# Sheet1.net
KiCad netlist of a schematic drawn in Altium Designer
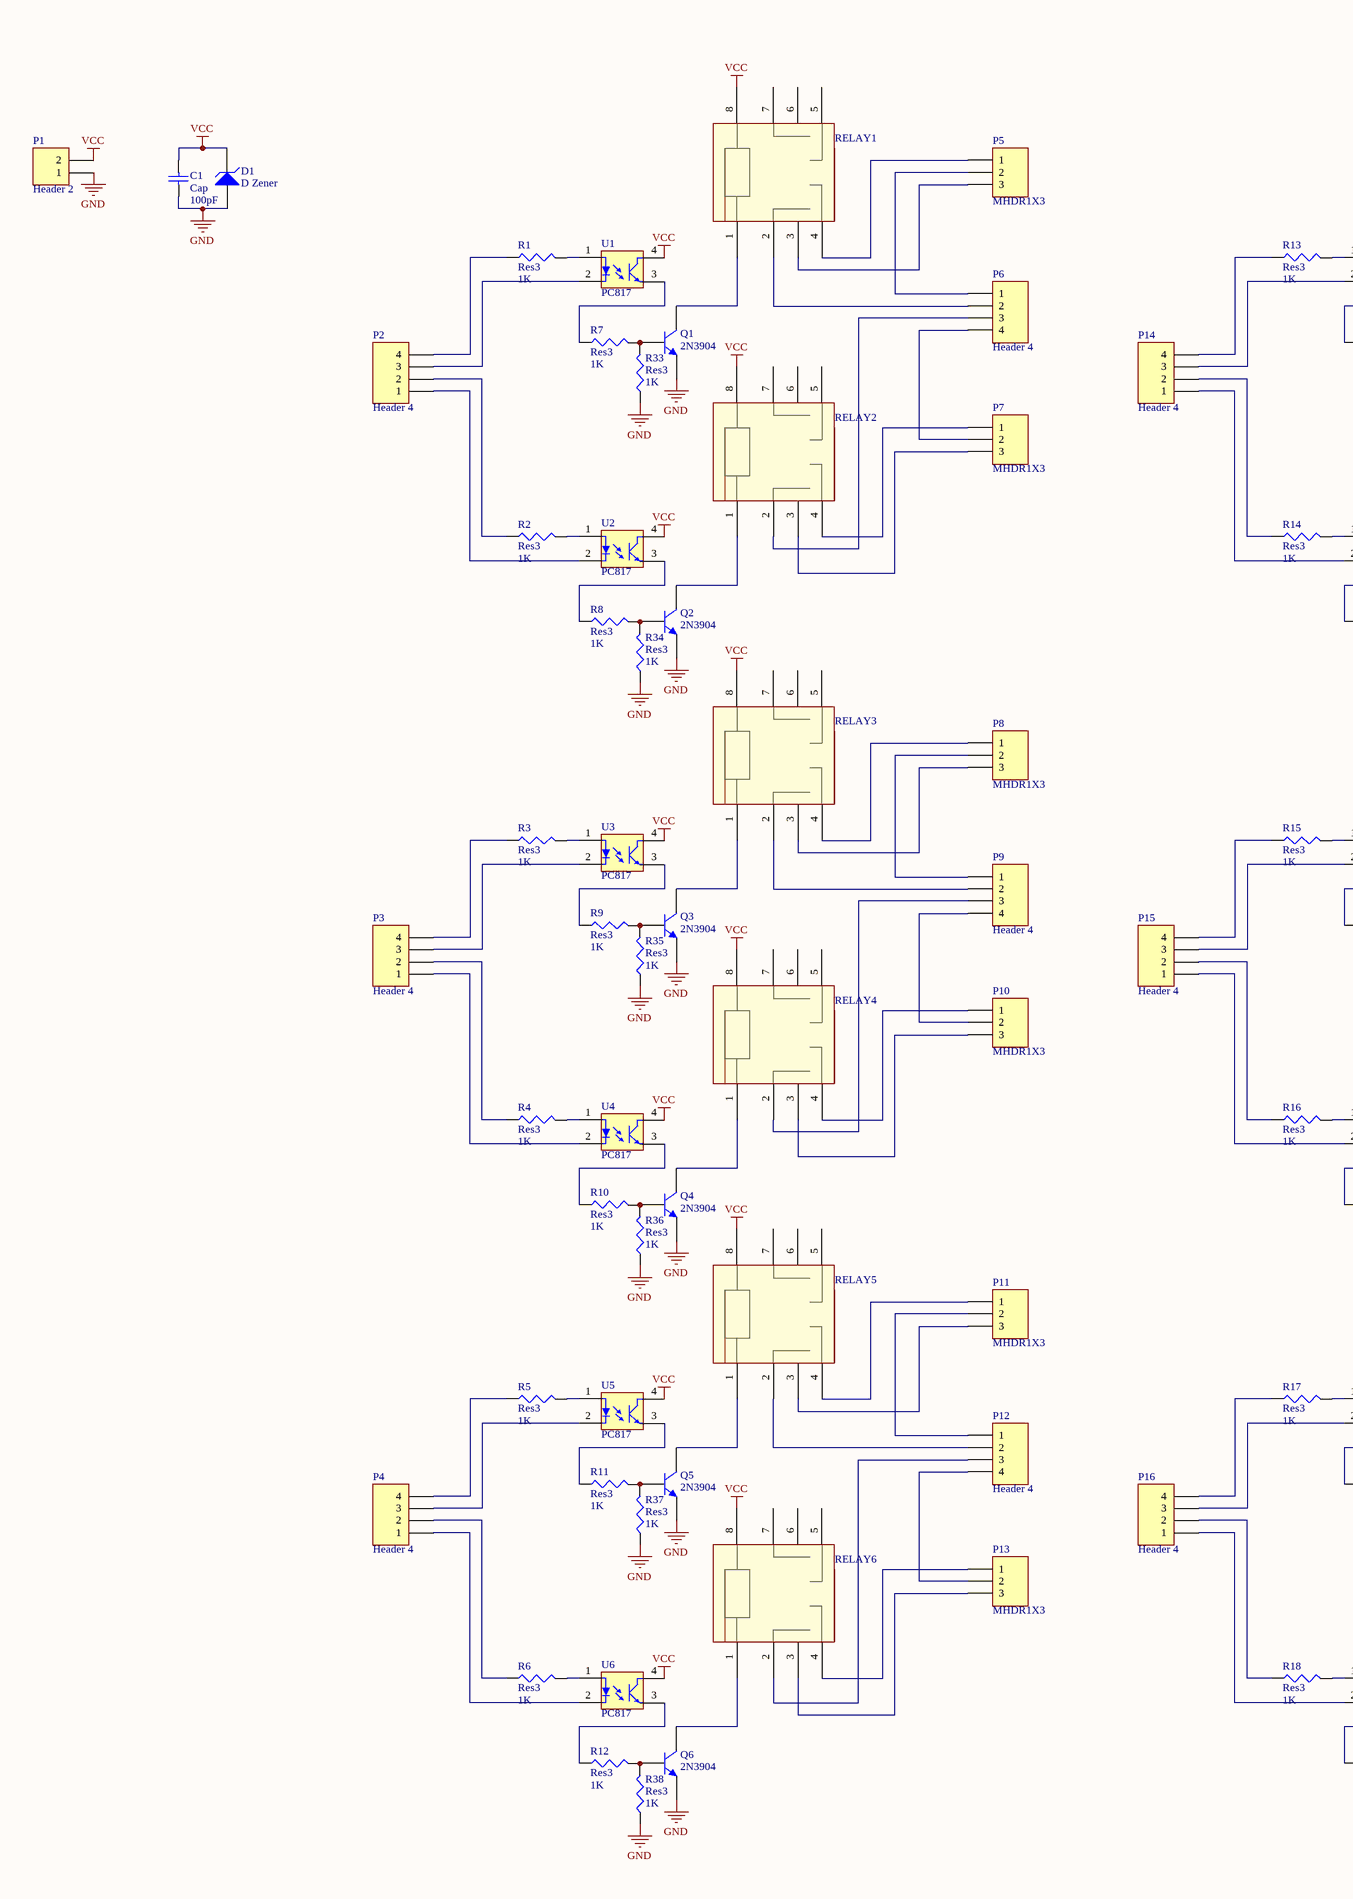
[diagram p0: Sheet1.SchDoc, left]
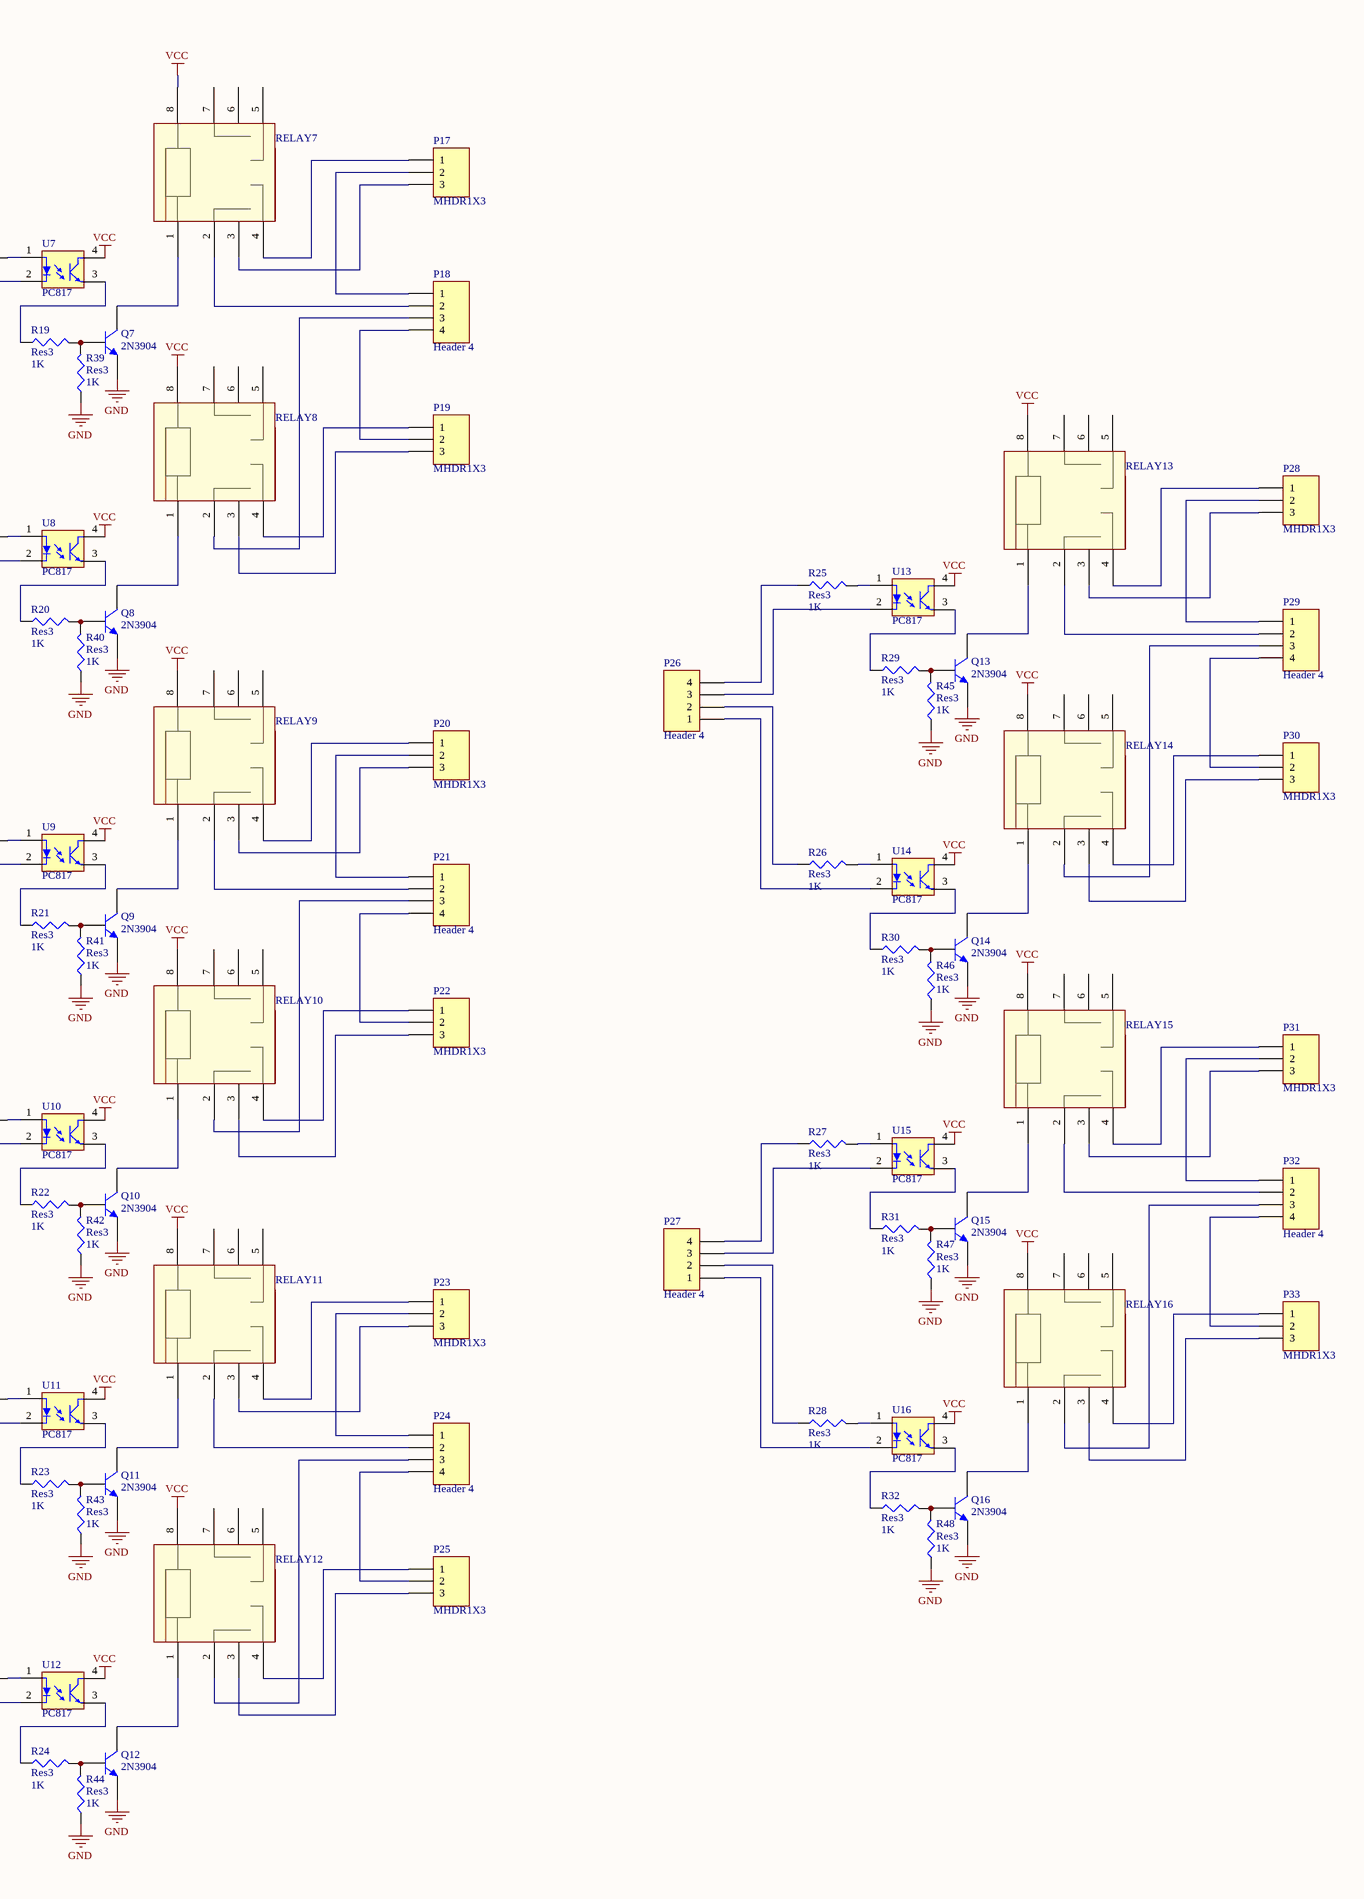
[diagram p1: Sheet1.SchDoc, right]

(export (version "E")
  (design (tool "Eeschema 10.0.6"))
  (components
    (comp (ref "C1")
      (value "Cap")
      (footprint "RAD-0.3")
      (description "Capacitor")
      (fields (field (name "ALTIUM_VALUE") "100pF") (field (name "PUBLISHER") "Altium Limited"))
      (libsource (lib "Miscellaneous Devices") (part "Cap"))
    )
    (comp (ref "D1")
      (value "D Zener")
      (footprint "DIODE-0.7")
      (description "Zener Diode")
      (fields (field (name "PUBLISHER") "Altium Limited"))
      (libsource (lib "Miscellaneous Devices") (part "D Zener"))
    )
    (comp (ref "P1")
      (value "Header 2")
      (footprint "CON2")
      (description "Header, 2-Pin")
      (fields (field (name "PUBLISHER") "Altium Limited"))
      (libsource (lib "Miscellaneous Connectors") (part "Header 2"))
    )
    (comp (ref "P2")
      (value "Header 4")
      (footprint "CON4")
      (description "Header, 4-Pin")
      (fields (field (name "PUBLISHER") "Altium Limited"))
      (libsource (lib "") (part "Header 4_1"))
    )
    (comp (ref "P3")
      (value "Header 4")
      (footprint "CON4")
      (description "Header, 4-Pin")
      (fields (field (name "PUBLISHER") "Altium Limited"))
      (libsource (lib "") (part "Header 4_1"))
    )
    (comp (ref "P4")
      (value "Header 4")
      (footprint "CON4")
      (description "Header, 4-Pin")
      (fields (field (name "PUBLISHER") "Altium Limited"))
      (libsource (lib "") (part "Header 4_1"))
    )
    (comp (ref "P5")
      (value "MHDR1X3")
      (footprint "MHDR1X3")
      (description "Header, 3-Pin")
      (fields (field (name "PUBLISHER") "Altium Limited"))
      (libsource (lib "Miscellaneous Connectors") (part "MHDR1X3"))
    )
    (comp (ref "P6")
      (value "Header 4")
      (footprint "CON4")
      (description "Header, 4-Pin")
      (fields (field (name "PUBLISHER") "Altium Limited"))
      (libsource (lib "Miscellaneous Connectors") (part "Header 4"))
    )
    (comp (ref "P7")
      (value "MHDR1X3")
      (footprint "MHDR1X3")
      (description "Header, 3-Pin")
      (fields (field (name "PUBLISHER") "Altium Limited"))
      (libsource (lib "Miscellaneous Connectors") (part "MHDR1X3"))
    )
    (comp (ref "P8")
      (value "MHDR1X3")
      (footprint "MHDR1X3")
      (description "Header, 3-Pin")
      (fields (field (name "PUBLISHER") "Altium Limited"))
      (libsource (lib "Miscellaneous Connectors") (part "MHDR1X3"))
    )
    (comp (ref "P9")
      (value "Header 4")
      (footprint "CON4")
      (description "Header, 4-Pin")
      (fields (field (name "PUBLISHER") "Altium Limited"))
      (libsource (lib "Miscellaneous Connectors") (part "Header 4"))
    )
    (comp (ref "P10")
      (value "MHDR1X3")
      (footprint "MHDR1X3")
      (description "Header, 3-Pin")
      (fields (field (name "PUBLISHER") "Altium Limited"))
      (libsource (lib "Miscellaneous Connectors") (part "MHDR1X3"))
    )
    (comp (ref "P11")
      (value "MHDR1X3")
      (footprint "MHDR1X3")
      (description "Header, 3-Pin")
      (fields (field (name "PUBLISHER") "Altium Limited"))
      (libsource (lib "Miscellaneous Connectors") (part "MHDR1X3"))
    )
    (comp (ref "P12")
      (value "Header 4")
      (footprint "CON4")
      (description "Header, 4-Pin")
      (fields (field (name "PUBLISHER") "Altium Limited"))
      (libsource (lib "Miscellaneous Connectors") (part "Header 4"))
    )
    (comp (ref "P13")
      (value "MHDR1X3")
      (footprint "MHDR1X3")
      (description "Header, 3-Pin")
      (fields (field (name "PUBLISHER") "Altium Limited"))
      (libsource (lib "Miscellaneous Connectors") (part "MHDR1X3"))
    )
    (comp (ref "P14")
      (value "Header 4")
      (footprint "CON4")
      (description "Header, 4-Pin")
      (fields (field (name "PUBLISHER") "Altium Limited"))
      (libsource (lib "") (part "Header 4_1"))
    )
    (comp (ref "P15")
      (value "Header 4")
      (footprint "CON4")
      (description "Header, 4-Pin")
      (fields (field (name "PUBLISHER") "Altium Limited"))
      (libsource (lib "") (part "Header 4_1"))
    )
    (comp (ref "P16")
      (value "Header 4")
      (footprint "CON4")
      (description "Header, 4-Pin")
      (fields (field (name "PUBLISHER") "Altium Limited"))
      (libsource (lib "") (part "Header 4_1"))
    )
    (comp (ref "P17")
      (value "MHDR1X3")
      (footprint "MHDR1X3")
      (description "Header, 3-Pin")
      (fields (field (name "PUBLISHER") "Altium Limited"))
      (libsource (lib "Miscellaneous Connectors") (part "MHDR1X3"))
    )
    (comp (ref "P18")
      (value "Header 4")
      (footprint "CON4")
      (description "Header, 4-Pin")
      (fields (field (name "PUBLISHER") "Altium Limited"))
      (libsource (lib "Miscellaneous Connectors") (part "Header 4"))
    )
    (comp (ref "P19")
      (value "MHDR1X3")
      (footprint "MHDR1X3")
      (description "Header, 3-Pin")
      (fields (field (name "PUBLISHER") "Altium Limited"))
      (libsource (lib "Miscellaneous Connectors") (part "MHDR1X3"))
    )
    (comp (ref "P20")
      (value "MHDR1X3")
      (footprint "MHDR1X3")
      (description "Header, 3-Pin")
      (fields (field (name "PUBLISHER") "Altium Limited"))
      (libsource (lib "Miscellaneous Connectors") (part "MHDR1X3"))
    )
    (comp (ref "P21")
      (value "Header 4")
      (footprint "CON4")
      (description "Header, 4-Pin")
      (fields (field (name "PUBLISHER") "Altium Limited"))
      (libsource (lib "Miscellaneous Connectors") (part "Header 4"))
    )
    (comp (ref "P22")
      (value "MHDR1X3")
      (footprint "MHDR1X3")
      (description "Header, 3-Pin")
      (fields (field (name "PUBLISHER") "Altium Limited"))
      (libsource (lib "Miscellaneous Connectors") (part "MHDR1X3"))
    )
    (comp (ref "P23")
      (value "MHDR1X3")
      (footprint "MHDR1X3")
      (description "Header, 3-Pin")
      (fields (field (name "PUBLISHER") "Altium Limited"))
      (libsource (lib "Miscellaneous Connectors") (part "MHDR1X3"))
    )
    (comp (ref "P24")
      (value "Header 4")
      (footprint "CON4")
      (description "Header, 4-Pin")
      (fields (field (name "PUBLISHER") "Altium Limited"))
      (libsource (lib "Miscellaneous Connectors") (part "Header 4"))
    )
    (comp (ref "P25")
      (value "MHDR1X3")
      (footprint "MHDR1X3")
      (description "Header, 3-Pin")
      (fields (field (name "PUBLISHER") "Altium Limited"))
      (libsource (lib "Miscellaneous Connectors") (part "MHDR1X3"))
    )
    (comp (ref "P26")
      (value "Header 4")
      (footprint "CON4")
      (description "Header, 4-Pin")
      (fields (field (name "PUBLISHER") "Altium Limited"))
      (libsource (lib "") (part "Header 4_1"))
    )
    (comp (ref "P27")
      (value "Header 4")
      (footprint "CON4")
      (description "Header, 4-Pin")
      (fields (field (name "PUBLISHER") "Altium Limited"))
      (libsource (lib "") (part "Header 4_1"))
    )
    (comp (ref "P28")
      (value "MHDR1X3")
      (footprint "MHDR1X3")
      (description "Header, 3-Pin")
      (fields (field (name "PUBLISHER") "Altium Limited"))
      (libsource (lib "Miscellaneous Connectors") (part "MHDR1X3"))
    )
    (comp (ref "P29")
      (value "Header 4")
      (footprint "CON4")
      (description "Header, 4-Pin")
      (fields (field (name "PUBLISHER") "Altium Limited"))
      (libsource (lib "Miscellaneous Connectors") (part "Header 4"))
    )
    (comp (ref "P30")
      (value "MHDR1X3")
      (footprint "MHDR1X3")
      (description "Header, 3-Pin")
      (fields (field (name "PUBLISHER") "Altium Limited"))
      (libsource (lib "Miscellaneous Connectors") (part "MHDR1X3"))
    )
    (comp (ref "P31")
      (value "MHDR1X3")
      (footprint "MHDR1X3")
      (description "Header, 3-Pin")
      (fields (field (name "PUBLISHER") "Altium Limited"))
      (libsource (lib "Miscellaneous Connectors") (part "MHDR1X3"))
    )
    (comp (ref "P32")
      (value "Header 4")
      (footprint "CON4")
      (description "Header, 4-Pin")
      (fields (field (name "PUBLISHER") "Altium Limited"))
      (libsource (lib "Miscellaneous Connectors") (part "Header 4"))
    )
    (comp (ref "P33")
      (value "MHDR1X3")
      (footprint "MHDR1X3")
      (description "Header, 3-Pin")
      (fields (field (name "PUBLISHER") "Altium Limited"))
      (libsource (lib "Miscellaneous Connectors") (part "MHDR1X3"))
    )
    (comp (ref "Q1")
      (value "2N3904")
      (footprint "QTO-92")
      (description "NPN General Purpose Amplifier")
      (fields (field (name "PUBLISHER") "Altium Limited"))
      (libsource (lib "Miscellaneous Devices") (part "2N3904"))
    )
    (comp (ref "Q2")
      (value "2N3904")
      (footprint "QTO-92")
      (description "NPN General Purpose Amplifier")
      (fields (field (name "PUBLISHER") "Altium Limited"))
      (libsource (lib "Miscellaneous Devices") (part "2N3904"))
    )
    (comp (ref "Q3")
      (value "2N3904")
      (footprint "QTO-92")
      (description "NPN General Purpose Amplifier")
      (fields (field (name "PUBLISHER") "Altium Limited"))
      (libsource (lib "Miscellaneous Devices") (part "2N3904"))
    )
    (comp (ref "Q4")
      (value "2N3904")
      (footprint "QTO-92")
      (description "NPN General Purpose Amplifier")
      (fields (field (name "PUBLISHER") "Altium Limited"))
      (libsource (lib "Miscellaneous Devices") (part "2N3904"))
    )
    (comp (ref "Q5")
      (value "2N3904")
      (footprint "QTO-92")
      (description "NPN General Purpose Amplifier")
      (fields (field (name "PUBLISHER") "Altium Limited"))
      (libsource (lib "Miscellaneous Devices") (part "2N3904"))
    )
    (comp (ref "Q6")
      (value "2N3904")
      (footprint "QTO-92")
      (description "NPN General Purpose Amplifier")
      (fields (field (name "PUBLISHER") "Altium Limited"))
      (libsource (lib "Miscellaneous Devices") (part "2N3904"))
    )
    (comp (ref "Q7")
      (value "2N3904")
      (footprint "QTO-92")
      (description "NPN General Purpose Amplifier")
      (fields (field (name "PUBLISHER") "Altium Limited"))
      (libsource (lib "Miscellaneous Devices") (part "2N3904"))
    )
    (comp (ref "Q8")
      (value "2N3904")
      (footprint "QTO-92")
      (description "NPN General Purpose Amplifier")
      (fields (field (name "PUBLISHER") "Altium Limited"))
      (libsource (lib "Miscellaneous Devices") (part "2N3904"))
    )
    (comp (ref "Q9")
      (value "2N3904")
      (footprint "QTO-92")
      (description "NPN General Purpose Amplifier")
      (fields (field (name "PUBLISHER") "Altium Limited"))
      (libsource (lib "Miscellaneous Devices") (part "2N3904"))
    )
    (comp (ref "Q10")
      (value "2N3904")
      (footprint "QTO-92")
      (description "NPN General Purpose Amplifier")
      (fields (field (name "PUBLISHER") "Altium Limited"))
      (libsource (lib "Miscellaneous Devices") (part "2N3904"))
    )
    (comp (ref "Q11")
      (value "2N3904")
      (footprint "QTO-92")
      (description "NPN General Purpose Amplifier")
      (fields (field (name "PUBLISHER") "Altium Limited"))
      (libsource (lib "Miscellaneous Devices") (part "2N3904"))
    )
    (comp (ref "Q12")
      (value "2N3904")
      (footprint "QTO-92")
      (description "NPN General Purpose Amplifier")
      (fields (field (name "PUBLISHER") "Altium Limited"))
      (libsource (lib "Miscellaneous Devices") (part "2N3904"))
    )
    (comp (ref "Q13")
      (value "2N3904")
      (footprint "QTO-92")
      (description "NPN General Purpose Amplifier")
      (fields (field (name "PUBLISHER") "Altium Limited"))
      (libsource (lib "Miscellaneous Devices") (part "2N3904"))
    )
    (comp (ref "Q14")
      (value "2N3904")
      (footprint "QTO-92")
      (description "NPN General Purpose Amplifier")
      (fields (field (name "PUBLISHER") "Altium Limited"))
      (libsource (lib "Miscellaneous Devices") (part "2N3904"))
    )
    (comp (ref "Q15")
      (value "2N3904")
      (footprint "QTO-92")
      (description "NPN General Purpose Amplifier")
      (fields (field (name "PUBLISHER") "Altium Limited"))
      (libsource (lib "Miscellaneous Devices") (part "2N3904"))
    )
    (comp (ref "Q16")
      (value "2N3904")
      (footprint "QTO-92")
      (description "NPN General Purpose Amplifier")
      (fields (field (name "PUBLISHER") "Altium Limited"))
      (libsource (lib "Miscellaneous Devices") (part "2N3904"))
    )
    (comp (ref "R1")
      (value "Res3")
      (footprint "C0805")
      (description "Resistor")
      (fields (field (name "ALTIUM_VALUE") "1K") (field (name "PUBLISHER") "Altium Limited"))
      (libsource (lib "Miscellaneous Devices") (part "Res3"))
    )
    (comp (ref "R2")
      (value "Res3")
      (footprint "C0805")
      (description "Resistor")
      (fields (field (name "ALTIUM_VALUE") "1K") (field (name "PUBLISHER") "Altium Limited"))
      (libsource (lib "Miscellaneous Devices") (part "Res3"))
    )
    (comp (ref "R3")
      (value "Res3")
      (footprint "C0805")
      (description "Resistor")
      (fields (field (name "ALTIUM_VALUE") "1K") (field (name "PUBLISHER") "Altium Limited"))
      (libsource (lib "Miscellaneous Devices") (part "Res3"))
    )
    (comp (ref "R4")
      (value "Res3")
      (footprint "C0805")
      (description "Resistor")
      (fields (field (name "ALTIUM_VALUE") "1K") (field (name "PUBLISHER") "Altium Limited"))
      (libsource (lib "Miscellaneous Devices") (part "Res3"))
    )
    (comp (ref "R5")
      (value "Res3")
      (footprint "C0805")
      (description "Resistor")
      (fields (field (name "ALTIUM_VALUE") "1K") (field (name "PUBLISHER") "Altium Limited"))
      (libsource (lib "Miscellaneous Devices") (part "Res3"))
    )
    (comp (ref "R6")
      (value "Res3")
      (footprint "C0805")
      (description "Resistor")
      (fields (field (name "ALTIUM_VALUE") "1K") (field (name "PUBLISHER") "Altium Limited"))
      (libsource (lib "Miscellaneous Devices") (part "Res3"))
    )
    (comp (ref "R7")
      (value "Res3")
      (footprint "C0805")
      (description "Resistor")
      (fields (field (name "ALTIUM_VALUE") "1K") (field (name "PUBLISHER") "Altium Limited"))
      (libsource (lib "Miscellaneous Devices") (part "Res3"))
    )
    (comp (ref "R8")
      (value "Res3")
      (footprint "C0805")
      (description "Resistor")
      (fields (field (name "ALTIUM_VALUE") "1K") (field (name "PUBLISHER") "Altium Limited"))
      (libsource (lib "Miscellaneous Devices") (part "Res3"))
    )
    (comp (ref "R9")
      (value "Res3")
      (footprint "C0805")
      (description "Resistor")
      (fields (field (name "ALTIUM_VALUE") "1K") (field (name "PUBLISHER") "Altium Limited"))
      (libsource (lib "Miscellaneous Devices") (part "Res3"))
    )
    (comp (ref "R10")
      (value "Res3")
      (footprint "C0805")
      (description "Resistor")
      (fields (field (name "ALTIUM_VALUE") "1K") (field (name "PUBLISHER") "Altium Limited"))
      (libsource (lib "Miscellaneous Devices") (part "Res3"))
    )
    (comp (ref "R11")
      (value "Res3")
      (footprint "C0805")
      (description "Resistor")
      (fields (field (name "ALTIUM_VALUE") "1K") (field (name "PUBLISHER") "Altium Limited"))
      (libsource (lib "Miscellaneous Devices") (part "Res3"))
    )
    (comp (ref "R12")
      (value "Res3")
      (footprint "C0805")
      (description "Resistor")
      (fields (field (name "ALTIUM_VALUE") "1K") (field (name "PUBLISHER") "Altium Limited"))
      (libsource (lib "Miscellaneous Devices") (part "Res3"))
    )
    (comp (ref "R13")
      (value "Res3")
      (footprint "C0805")
      (description "Resistor")
      (fields (field (name "ALTIUM_VALUE") "1K") (field (name "PUBLISHER") "Altium Limited"))
      (libsource (lib "Miscellaneous Devices") (part "Res3"))
    )
    (comp (ref "R14")
      (value "Res3")
      (footprint "C0805")
      (description "Resistor")
      (fields (field (name "ALTIUM_VALUE") "1K") (field (name "PUBLISHER") "Altium Limited"))
      (libsource (lib "Miscellaneous Devices") (part "Res3"))
    )
    (comp (ref "R15")
      (value "Res3")
      (footprint "C0805")
      (description "Resistor")
      (fields (field (name "ALTIUM_VALUE") "1K") (field (name "PUBLISHER") "Altium Limited"))
      (libsource (lib "Miscellaneous Devices") (part "Res3"))
    )
    (comp (ref "R16")
      (value "Res3")
      (footprint "C0805")
      (description "Resistor")
      (fields (field (name "ALTIUM_VALUE") "1K") (field (name "PUBLISHER") "Altium Limited"))
      (libsource (lib "Miscellaneous Devices") (part "Res3"))
    )
    (comp (ref "R17")
      (value "Res3")
      (footprint "C0805")
      (description "Resistor")
      (fields (field (name "ALTIUM_VALUE") "1K") (field (name "PUBLISHER") "Altium Limited"))
      (libsource (lib "Miscellaneous Devices") (part "Res3"))
    )
    (comp (ref "R18")
      (value "Res3")
      (footprint "C0805")
      (description "Resistor")
      (fields (field (name "ALTIUM_VALUE") "1K") (field (name "PUBLISHER") "Altium Limited"))
      (libsource (lib "Miscellaneous Devices") (part "Res3"))
    )
    (comp (ref "R19")
      (value "Res3")
      (footprint "C0805")
      (description "Resistor")
      (fields (field (name "ALTIUM_VALUE") "1K") (field (name "PUBLISHER") "Altium Limited"))
      (libsource (lib "Miscellaneous Devices") (part "Res3"))
    )
    (comp (ref "R20")
      (value "Res3")
      (footprint "C0805")
      (description "Resistor")
      (fields (field (name "ALTIUM_VALUE") "1K") (field (name "PUBLISHER") "Altium Limited"))
      (libsource (lib "Miscellaneous Devices") (part "Res3"))
    )
    (comp (ref "R21")
      (value "Res3")
      (footprint "C0805")
      (description "Resistor")
      (fields (field (name "ALTIUM_VALUE") "1K") (field (name "PUBLISHER") "Altium Limited"))
      (libsource (lib "Miscellaneous Devices") (part "Res3"))
    )
    (comp (ref "R22")
      (value "Res3")
      (footprint "C0805")
      (description "Resistor")
      (fields (field (name "ALTIUM_VALUE") "1K") (field (name "PUBLISHER") "Altium Limited"))
      (libsource (lib "Miscellaneous Devices") (part "Res3"))
    )
    (comp (ref "R23")
      (value "Res3")
      (footprint "C0805")
      (description "Resistor")
      (fields (field (name "ALTIUM_VALUE") "1K") (field (name "PUBLISHER") "Altium Limited"))
      (libsource (lib "Miscellaneous Devices") (part "Res3"))
    )
    (comp (ref "R24")
      (value "Res3")
      (footprint "C0805")
      (description "Resistor")
      (fields (field (name "ALTIUM_VALUE") "1K") (field (name "PUBLISHER") "Altium Limited"))
      (libsource (lib "Miscellaneous Devices") (part "Res3"))
    )
    (comp (ref "R25")
      (value "Res3")
      (footprint "C0805")
      (description "Resistor")
      (fields (field (name "ALTIUM_VALUE") "1K") (field (name "PUBLISHER") "Altium Limited"))
      (libsource (lib "Miscellaneous Devices") (part "Res3"))
    )
    (comp (ref "R26")
      (value "Res3")
      (footprint "C0805")
      (description "Resistor")
      (fields (field (name "ALTIUM_VALUE") "1K") (field (name "PUBLISHER") "Altium Limited"))
      (libsource (lib "Miscellaneous Devices") (part "Res3"))
    )
    (comp (ref "R27")
      (value "Res3")
      (footprint "C0805")
      (description "Resistor")
      (fields (field (name "ALTIUM_VALUE") "1K") (field (name "PUBLISHER") "Altium Limited"))
      (libsource (lib "Miscellaneous Devices") (part "Res3"))
    )
    (comp (ref "R28")
      (value "Res3")
      (footprint "C0805")
      (description "Resistor")
      (fields (field (name "ALTIUM_VALUE") "1K") (field (name "PUBLISHER") "Altium Limited"))
      (libsource (lib "Miscellaneous Devices") (part "Res3"))
    )
    (comp (ref "R29")
      (value "Res3")
      (footprint "C0805")
      (description "Resistor")
      (fields (field (name "ALTIUM_VALUE") "1K") (field (name "PUBLISHER") "Altium Limited"))
      (libsource (lib "Miscellaneous Devices") (part "Res3"))
    )
    (comp (ref "R30")
      (value "Res3")
      (footprint "C0805")
      (description "Resistor")
      (fields (field (name "ALTIUM_VALUE") "1K") (field (name "PUBLISHER") "Altium Limited"))
      (libsource (lib "Miscellaneous Devices") (part "Res3"))
    )
    (comp (ref "R31")
      (value "Res3")
      (footprint "C0805")
      (description "Resistor")
      (fields (field (name "ALTIUM_VALUE") "1K") (field (name "PUBLISHER") "Altium Limited"))
      (libsource (lib "Miscellaneous Devices") (part "Res3"))
    )
    (comp (ref "R32")
      (value "Res3")
      (footprint "C0805")
      (description "Resistor")
      (fields (field (name "ALTIUM_VALUE") "1K") (field (name "PUBLISHER") "Altium Limited"))
      (libsource (lib "Miscellaneous Devices") (part "Res3"))
    )
    (comp (ref "R33")
      (value "Res3")
      (footprint "C0805")
      (description "Resistor")
      (fields (field (name "ALTIUM_VALUE") "1K") (field (name "PUBLISHER") "Altium Limited"))
      (libsource (lib "Miscellaneous Devices") (part "Res3"))
    )
    (comp (ref "R34")
      (value "Res3")
      (footprint "C0805")
      (description "Resistor")
      (fields (field (name "ALTIUM_VALUE") "1K") (field (name "PUBLISHER") "Altium Limited"))
      (libsource (lib "Miscellaneous Devices") (part "Res3"))
    )
    (comp (ref "R35")
      (value "Res3")
      (footprint "C0805")
      (description "Resistor")
      (fields (field (name "ALTIUM_VALUE") "1K") (field (name "PUBLISHER") "Altium Limited"))
      (libsource (lib "Miscellaneous Devices") (part "Res3"))
    )
    (comp (ref "R36")
      (value "Res3")
      (footprint "C0805")
      (description "Resistor")
      (fields (field (name "ALTIUM_VALUE") "1K") (field (name "PUBLISHER") "Altium Limited"))
      (libsource (lib "Miscellaneous Devices") (part "Res3"))
    )
    (comp (ref "R37")
      (value "Res3")
      (footprint "C0805")
      (description "Resistor")
      (fields (field (name "ALTIUM_VALUE") "1K") (field (name "PUBLISHER") "Altium Limited"))
      (libsource (lib "Miscellaneous Devices") (part "Res3"))
    )
    (comp (ref "R38")
      (value "Res3")
      (footprint "C0805")
      (description "Resistor")
      (fields (field (name "ALTIUM_VALUE") "1K") (field (name "PUBLISHER") "Altium Limited"))
      (libsource (lib "Miscellaneous Devices") (part "Res3"))
    )
    (comp (ref "R39")
      (value "Res3")
      (footprint "C0805")
      (description "Resistor")
      (fields (field (name "ALTIUM_VALUE") "1K") (field (name "PUBLISHER") "Altium Limited"))
      (libsource (lib "Miscellaneous Devices") (part "Res3"))
    )
    (comp (ref "R40")
      (value "Res3")
      (footprint "C0805")
      (description "Resistor")
      (fields (field (name "ALTIUM_VALUE") "1K") (field (name "PUBLISHER") "Altium Limited"))
      (libsource (lib "Miscellaneous Devices") (part "Res3"))
    )
    (comp (ref "R41")
      (value "Res3")
      (footprint "C0805")
      (description "Resistor")
      (fields (field (name "ALTIUM_VALUE") "1K") (field (name "PUBLISHER") "Altium Limited"))
      (libsource (lib "Miscellaneous Devices") (part "Res3"))
    )
    (comp (ref "R42")
      (value "Res3")
      (footprint "C0805")
      (description "Resistor")
      (fields (field (name "ALTIUM_VALUE") "1K") (field (name "PUBLISHER") "Altium Limited"))
      (libsource (lib "Miscellaneous Devices") (part "Res3"))
    )
    (comp (ref "R43")
      (value "Res3")
      (footprint "C0805")
      (description "Resistor")
      (fields (field (name "ALTIUM_VALUE") "1K") (field (name "PUBLISHER") "Altium Limited"))
      (libsource (lib "Miscellaneous Devices") (part "Res3"))
    )
    (comp (ref "R44")
      (value "Res3")
      (footprint "C0805")
      (description "Resistor")
      (fields (field (name "ALTIUM_VALUE") "1K") (field (name "PUBLISHER") "Altium Limited"))
      (libsource (lib "Miscellaneous Devices") (part "Res3"))
    )
    (comp (ref "R45")
      (value "Res3")
      (footprint "C0805")
      (description "Resistor")
      (fields (field (name "ALTIUM_VALUE") "1K") (field (name "PUBLISHER") "Altium Limited"))
      (libsource (lib "Miscellaneous Devices") (part "Res3"))
    )
    (comp (ref "R46")
      (value "Res3")
      (footprint "C0805")
      (description "Resistor")
      (fields (field (name "ALTIUM_VALUE") "1K") (field (name "PUBLISHER") "Altium Limited"))
      (libsource (lib "Miscellaneous Devices") (part "Res3"))
    )
    (comp (ref "R47")
      (value "Res3")
      (footprint "C0805")
      (description "Resistor")
      (fields (field (name "ALTIUM_VALUE") "1K") (field (name "PUBLISHER") "Altium Limited"))
      (libsource (lib "Miscellaneous Devices") (part "Res3"))
    )
    (comp (ref "R48")
      (value "Res3")
      (footprint "C0805")
      (description "Resistor")
      (fields (field (name "ALTIUM_VALUE") "1K") (field (name "PUBLISHER") "Altium Limited"))
      (libsource (lib "Miscellaneous Devices") (part "Res3"))
    )
    (comp (ref "RELAY1")
      (value "RY12W-K")
      (footprint "RY-Series")
      (libsource (lib "dung_maker_2018") (part "RY12W-K"))
    )
    (comp (ref "RELAY2")
      (value "RY12W-K")
      (footprint "RY-Series")
      (libsource (lib "dung_maker_2018") (part "RY12W-K"))
    )
    (comp (ref "RELAY3")
      (value "RY12W-K")
      (footprint "RY-Series")
      (libsource (lib "dung_maker_2018") (part "RY12W-K"))
    )
    (comp (ref "RELAY4")
      (value "RY12W-K")
      (footprint "RY-Series")
      (libsource (lib "dung_maker_2018") (part "RY12W-K"))
    )
    (comp (ref "RELAY5")
      (value "RY12W-K")
      (footprint "RY-Series")
      (libsource (lib "dung_maker_2018") (part "RY12W-K"))
    )
    (comp (ref "RELAY6")
      (value "RY12W-K")
      (footprint "RY-Series")
      (libsource (lib "dung_maker_2018") (part "RY12W-K"))
    )
    (comp (ref "RELAY7")
      (value "RY12W-K")
      (footprint "RY-Series")
      (libsource (lib "dung_maker_2018") (part "RY12W-K"))
    )
    (comp (ref "RELAY8")
      (value "RY12W-K")
      (footprint "RY-Series")
      (libsource (lib "dung_maker_2018") (part "RY12W-K"))
    )
    (comp (ref "RELAY9")
      (value "RY12W-K")
      (footprint "RY-Series")
      (libsource (lib "dung_maker_2018") (part "RY12W-K"))
    )
    (comp (ref "RELAY10")
      (value "RY12W-K")
      (footprint "RY-Series")
      (libsource (lib "dung_maker_2018") (part "RY12W-K"))
    )
    (comp (ref "RELAY11")
      (value "RY12W-K")
      (footprint "RY-Series")
      (libsource (lib "dung_maker_2018") (part "RY12W-K"))
    )
    (comp (ref "RELAY12")
      (value "RY12W-K")
      (footprint "RY-Series")
      (libsource (lib "dung_maker_2018") (part "RY12W-K"))
    )
    (comp (ref "RELAY13")
      (value "RY12W-K")
      (footprint "RY-Series")
      (libsource (lib "dung_maker_2018") (part "RY12W-K"))
    )
    (comp (ref "RELAY14")
      (value "RY12W-K")
      (footprint "RY-Series")
      (libsource (lib "dung_maker_2018") (part "RY12W-K"))
    )
    (comp (ref "RELAY15")
      (value "RY12W-K")
      (footprint "RY-Series")
      (libsource (lib "dung_maker_2018") (part "RY12W-K"))
    )
    (comp (ref "RELAY16")
      (value "RY12W-K")
      (footprint "RY-Series")
      (libsource (lib "dung_maker_2018") (part "RY12W-K"))
    )
    (comp (ref "U1")
      (value "PC817")
      (footprint "DIP4")
      (fields (field (name "Comment") "OPTO"))
      (libsource (lib "dung_maker_2018") (part "OPTO_PC817"))
    )
    (comp (ref "U2")
      (value "PC817")
      (footprint "DIP4")
      (fields (field (name "Comment") "OPTO"))
      (libsource (lib "dung_maker_2018") (part "OPTO_PC817"))
    )
    (comp (ref "U3")
      (value "PC817")
      (footprint "DIP4")
      (fields (field (name "Comment") "OPTO"))
      (libsource (lib "dung_maker_2018") (part "OPTO_PC817"))
    )
    (comp (ref "U4")
      (value "PC817")
      (footprint "DIP4")
      (fields (field (name "Comment") "OPTO"))
      (libsource (lib "dung_maker_2018") (part "OPTO_PC817"))
    )
    (comp (ref "U5")
      (value "PC817")
      (footprint "DIP4")
      (fields (field (name "Comment") "OPTO"))
      (libsource (lib "dung_maker_2018") (part "OPTO_PC817"))
    )
    (comp (ref "U6")
      (value "PC817")
      (footprint "DIP4")
      (fields (field (name "Comment") "OPTO"))
      (libsource (lib "dung_maker_2018") (part "OPTO_PC817"))
    )
    (comp (ref "U7")
      (value "PC817")
      (footprint "DIP4")
      (fields (field (name "Comment") "OPTO"))
      (libsource (lib "dung_maker_2018") (part "OPTO_PC817"))
    )
    (comp (ref "U8")
      (value "PC817")
      (footprint "DIP4")
      (fields (field (name "Comment") "OPTO"))
      (libsource (lib "dung_maker_2018") (part "OPTO_PC817"))
    )
    (comp (ref "U9")
      (value "PC817")
      (footprint "DIP4")
      (fields (field (name "Comment") "OPTO"))
      (libsource (lib "dung_maker_2018") (part "OPTO_PC817"))
    )
    (comp (ref "U10")
      (value "PC817")
      (footprint "DIP4")
      (fields (field (name "Comment") "OPTO"))
      (libsource (lib "dung_maker_2018") (part "OPTO_PC817"))
    )
    (comp (ref "U11")
      (value "PC817")
      (footprint "DIP4")
      (fields (field (name "Comment") "OPTO"))
      (libsource (lib "dung_maker_2018") (part "OPTO_PC817"))
    )
    (comp (ref "U12")
      (value "PC817")
      (footprint "DIP4")
      (fields (field (name "Comment") "OPTO"))
      (libsource (lib "dung_maker_2018") (part "OPTO_PC817"))
    )
    (comp (ref "U13")
      (value "PC817")
      (footprint "DIP4")
      (fields (field (name "Comment") "OPTO"))
      (libsource (lib "dung_maker_2018") (part "OPTO_PC817"))
    )
    (comp (ref "U14")
      (value "PC817")
      (footprint "DIP4")
      (fields (field (name "Comment") "OPTO"))
      (libsource (lib "dung_maker_2018") (part "OPTO_PC817"))
    )
    (comp (ref "U15")
      (value "PC817")
      (footprint "DIP4")
      (fields (field (name "Comment") "OPTO"))
      (libsource (lib "dung_maker_2018") (part "OPTO_PC817"))
    )
    (comp (ref "U16")
      (value "PC817")
      (footprint "DIP4")
      (fields (field (name "Comment") "OPTO"))
      (libsource (lib "dung_maker_2018") (part "OPTO_PC817"))
    )
  )
  (nets
    (net (code "1") (name "GND") (class "Default")
      (node (ref "C1") (pin "1") (pinfunction "1_1") (pintype "passive"))
      (node (ref "D1") (pin "1") (pinfunction "A_1") (pintype "passive"))
      (node (ref "P1") (pin "1") (pinfunction "1_1") (pintype "passive"))
      (node (ref "Q1") (pin "1") (pinfunction "E_1") (pintype "passive"))
      (node (ref "Q10") (pin "1") (pinfunction "E_1") (pintype "passive"))
      (node (ref "Q11") (pin "1") (pinfunction "E_1") (pintype "passive"))
      (node (ref "Q12") (pin "1") (pinfunction "E_1") (pintype "passive"))
      (node (ref "Q13") (pin "1") (pinfunction "E_1") (pintype "passive"))
      (node (ref "Q14") (pin "1") (pinfunction "E_1") (pintype "passive"))
      (node (ref "Q15") (pin "1") (pinfunction "E_1") (pintype "passive"))
      (node (ref "Q16") (pin "1") (pinfunction "E_1") (pintype "passive"))
      (node (ref "Q2") (pin "1") (pinfunction "E_1") (pintype "passive"))
      (node (ref "Q3") (pin "1") (pinfunction "E_1") (pintype "passive"))
      (node (ref "Q4") (pin "1") (pinfunction "E_1") (pintype "passive"))
      (node (ref "Q5") (pin "1") (pinfunction "E_1") (pintype "passive"))
      (node (ref "Q6") (pin "1") (pinfunction "E_1") (pintype "passive"))
      (node (ref "Q7") (pin "1") (pinfunction "E_1") (pintype "passive"))
      (node (ref "Q8") (pin "1") (pinfunction "E_1") (pintype "passive"))
      (node (ref "Q9") (pin "1") (pinfunction "E_1") (pintype "passive"))
      (node (ref "R33") (pin "1") (pinfunction "1_1") (pintype "passive"))
      (node (ref "R34") (pin "1") (pinfunction "1_1") (pintype "passive"))
      (node (ref "R35") (pin "1") (pinfunction "1_1") (pintype "passive"))
      (node (ref "R36") (pin "1") (pinfunction "1_1") (pintype "passive"))
      (node (ref "R37") (pin "1") (pinfunction "1_1") (pintype "passive"))
      (node (ref "R38") (pin "1") (pinfunction "1_1") (pintype "passive"))
      (node (ref "R39") (pin "1") (pinfunction "1_1") (pintype "passive"))
      (node (ref "R40") (pin "1") (pinfunction "1_1") (pintype "passive"))
      (node (ref "R41") (pin "1") (pinfunction "1_1") (pintype "passive"))
      (node (ref "R42") (pin "1") (pinfunction "1_1") (pintype "passive"))
      (node (ref "R43") (pin "1") (pinfunction "1_1") (pintype "passive"))
      (node (ref "R44") (pin "1") (pinfunction "1_1") (pintype "passive"))
      (node (ref "R45") (pin "1") (pinfunction "1_1") (pintype "passive"))
      (node (ref "R46") (pin "1") (pinfunction "1_1") (pintype "passive"))
      (node (ref "R47") (pin "1") (pinfunction "1_1") (pintype "passive"))
      (node (ref "R48") (pin "1") (pinfunction "1_1") (pintype "passive"))
    )
    (net (code "2") (name "Net-(P2-Pad1)") (class "Default")
      (node (ref "P2") (pin "1") (pinfunction "1_1") (pintype "passive"))
      (node (ref "U2") (pin "2") (pinfunction "C_2") (pintype "passive"))
    )
    (net (code "3") (name "Net-(P2-Pad2)") (class "Default")
      (node (ref "P2") (pin "2") (pinfunction "2_2") (pintype "passive"))
      (node (ref "R2") (pin "1") (pinfunction "1_1") (pintype "passive"))
    )
    (net (code "4") (name "Net-(P2-Pad3)") (class "Default")
      (node (ref "P2") (pin "3") (pinfunction "3_3") (pintype "passive"))
      (node (ref "U1") (pin "2") (pinfunction "C_2") (pintype "passive"))
    )
    (net (code "5") (name "Net-(P2-Pad4)") (class "Default")
      (node (ref "P2") (pin "4") (pinfunction "4_4") (pintype "passive"))
      (node (ref "R1") (pin "1") (pinfunction "1_1") (pintype "passive"))
    )
    (net (code "6") (name "Net-(P3-Pad1)") (class "Default")
      (node (ref "P3") (pin "1") (pinfunction "1_1") (pintype "passive"))
      (node (ref "U4") (pin "2") (pinfunction "C_2") (pintype "passive"))
    )
    (net (code "7") (name "Net-(P3-Pad2)") (class "Default")
      (node (ref "P3") (pin "2") (pinfunction "2_2") (pintype "passive"))
      (node (ref "R4") (pin "1") (pinfunction "1_1") (pintype "passive"))
    )
    (net (code "8") (name "Net-(P3-Pad3)") (class "Default")
      (node (ref "P3") (pin "3") (pinfunction "3_3") (pintype "passive"))
      (node (ref "U3") (pin "2") (pinfunction "C_2") (pintype "passive"))
    )
    (net (code "9") (name "Net-(P3-Pad4)") (class "Default")
      (node (ref "P3") (pin "4") (pinfunction "4_4") (pintype "passive"))
      (node (ref "R3") (pin "1") (pinfunction "1_1") (pintype "passive"))
    )
    (net (code "10") (name "Net-(P4-Pad1)") (class "Default")
      (node (ref "P4") (pin "1") (pinfunction "1_1") (pintype "passive"))
      (node (ref "U6") (pin "2") (pinfunction "C_2") (pintype "passive"))
    )
    (net (code "11") (name "Net-(P4-Pad2)") (class "Default")
      (node (ref "P4") (pin "2") (pinfunction "2_2") (pintype "passive"))
      (node (ref "R6") (pin "1") (pinfunction "1_1") (pintype "passive"))
    )
    (net (code "12") (name "Net-(P4-Pad3)") (class "Default")
      (node (ref "P4") (pin "3") (pinfunction "3_3") (pintype "passive"))
      (node (ref "U5") (pin "2") (pinfunction "C_2") (pintype "passive"))
    )
    (net (code "13") (name "Net-(P4-Pad4)") (class "Default")
      (node (ref "P4") (pin "4") (pinfunction "4_4") (pintype "passive"))
      (node (ref "R5") (pin "1") (pinfunction "1_1") (pintype "passive"))
    )
    (net (code "14") (name "Net-(P5-Pad1)") (class "Default")
      (node (ref "P5") (pin "1") (pinfunction "1_1") (pintype "passive"))
      (node (ref "RELAY1") (pin "4") (pinfunction "4_4") (pintype "passive"))
    )
    (net (code "15") (name "Net-(P5-Pad2)") (class "Default")
      (node (ref "P5") (pin "2") (pinfunction "2_2") (pintype "passive"))
      (node (ref "P6") (pin "1") (pinfunction "1_1") (pintype "passive"))
    )
    (net (code "16") (name "Net-(P5-Pad3)") (class "Default")
      (node (ref "P5") (pin "3") (pinfunction "3_3") (pintype "passive"))
      (node (ref "RELAY1") (pin "3") (pinfunction "3_3") (pintype "passive"))
    )
    (net (code "17") (name "Net-(P6-Pad2)") (class "Default")
      (node (ref "P6") (pin "2") (pinfunction "2_2") (pintype "passive"))
      (node (ref "RELAY1") (pin "2") (pinfunction "2_2") (pintype "passive"))
    )
    (net (code "18") (name "Net-(P6-Pad3)") (class "Default")
      (node (ref "P6") (pin "3") (pinfunction "3_3") (pintype "passive"))
      (node (ref "RELAY2") (pin "2") (pinfunction "2_2") (pintype "passive"))
    )
    (net (code "19") (name "Net-(P6-Pad4)") (class "Default")
      (node (ref "P6") (pin "4") (pinfunction "4_4") (pintype "passive"))
      (node (ref "P7") (pin "2") (pinfunction "2_2") (pintype "passive"))
    )
    (net (code "20") (name "Net-(P7-Pad1)") (class "Default")
      (node (ref "P7") (pin "1") (pinfunction "1_1") (pintype "passive"))
      (node (ref "RELAY2") (pin "4") (pinfunction "4_4") (pintype "passive"))
    )
    (net (code "21") (name "Net-(P7-Pad3)") (class "Default")
      (node (ref "P7") (pin "3") (pinfunction "3_3") (pintype "passive"))
      (node (ref "RELAY2") (pin "3") (pinfunction "3_3") (pintype "passive"))
    )
    (net (code "22") (name "Net-(P8-Pad1)") (class "Default")
      (node (ref "P8") (pin "1") (pinfunction "1_1") (pintype "passive"))
      (node (ref "RELAY3") (pin "4") (pinfunction "4_4") (pintype "passive"))
    )
    (net (code "23") (name "Net-(P8-Pad2)") (class "Default")
      (node (ref "P8") (pin "2") (pinfunction "2_2") (pintype "passive"))
      (node (ref "P9") (pin "1") (pinfunction "1_1") (pintype "passive"))
    )
    (net (code "24") (name "Net-(P8-Pad3)") (class "Default")
      (node (ref "P8") (pin "3") (pinfunction "3_3") (pintype "passive"))
      (node (ref "RELAY3") (pin "3") (pinfunction "3_3") (pintype "passive"))
    )
    (net (code "25") (name "Net-(P9-Pad2)") (class "Default")
      (node (ref "P9") (pin "2") (pinfunction "2_2") (pintype "passive"))
      (node (ref "RELAY3") (pin "2") (pinfunction "2_2") (pintype "passive"))
    )
    (net (code "26") (name "Net-(P9-Pad3)") (class "Default")
      (node (ref "P9") (pin "3") (pinfunction "3_3") (pintype "passive"))
      (node (ref "RELAY4") (pin "2") (pinfunction "2_2") (pintype "passive"))
    )
    (net (code "27") (name "Net-(P10-Pad1)") (class "Default")
      (node (ref "P10") (pin "1") (pinfunction "1_1") (pintype "passive"))
      (node (ref "RELAY4") (pin "4") (pinfunction "4_4") (pintype "passive"))
    )
    (net (code "28") (name "Net-(P10-Pad2)") (class "Default")
      (node (ref "P10") (pin "2") (pinfunction "2_2") (pintype "passive"))
      (node (ref "P9") (pin "4") (pinfunction "4_4") (pintype "passive"))
    )
    (net (code "29") (name "Net-(P10-Pad3)") (class "Default")
      (node (ref "P10") (pin "3") (pinfunction "3_3") (pintype "passive"))
      (node (ref "RELAY4") (pin "3") (pinfunction "3_3") (pintype "passive"))
    )
    (net (code "30") (name "Net-(P11-Pad1)") (class "Default")
      (node (ref "P11") (pin "1") (pinfunction "1_1") (pintype "passive"))
      (node (ref "RELAY5") (pin "4") (pinfunction "4_4") (pintype "passive"))
    )
    (net (code "31") (name "Net-(P11-Pad2)") (class "Default")
      (node (ref "P11") (pin "2") (pinfunction "2_2") (pintype "passive"))
      (node (ref "P12") (pin "1") (pinfunction "1_1") (pintype "passive"))
    )
    (net (code "32") (name "Net-(P11-Pad3)") (class "Default")
      (node (ref "P11") (pin "3") (pinfunction "3_3") (pintype "passive"))
      (node (ref "RELAY5") (pin "3") (pinfunction "3_3") (pintype "passive"))
    )
    (net (code "33") (name "Net-(P12-Pad2)") (class "Default")
      (node (ref "P12") (pin "2") (pinfunction "2_2") (pintype "passive"))
      (node (ref "RELAY5") (pin "2") (pinfunction "2_2") (pintype "passive"))
    )
    (net (code "34") (name "Net-(P12-Pad3)") (class "Default")
      (node (ref "P12") (pin "3") (pinfunction "3_3") (pintype "passive"))
      (node (ref "RELAY6") (pin "2") (pinfunction "2_2") (pintype "passive"))
    )
    (net (code "35") (name "Net-(P12-Pad4)") (class "Default")
      (node (ref "P12") (pin "4") (pinfunction "4_4") (pintype "passive"))
      (node (ref "P13") (pin "2") (pinfunction "2_2") (pintype "passive"))
    )
    (net (code "36") (name "Net-(P13-Pad1)") (class "Default")
      (node (ref "P13") (pin "1") (pinfunction "1_1") (pintype "passive"))
      (node (ref "RELAY6") (pin "4") (pinfunction "4_4") (pintype "passive"))
    )
    (net (code "37") (name "Net-(P13-Pad3)") (class "Default")
      (node (ref "P13") (pin "3") (pinfunction "3_3") (pintype "passive"))
      (node (ref "RELAY6") (pin "3") (pinfunction "3_3") (pintype "passive"))
    )
    (net (code "38") (name "Net-(P14-Pad1)") (class "Default")
      (node (ref "P14") (pin "1") (pinfunction "1_1") (pintype "passive"))
      (node (ref "U8") (pin "2") (pinfunction "C_2") (pintype "passive"))
    )
    (net (code "39") (name "Net-(P14-Pad2)") (class "Default")
      (node (ref "P14") (pin "2") (pinfunction "2_2") (pintype "passive"))
      (node (ref "R14") (pin "1") (pinfunction "1_1") (pintype "passive"))
    )
    (net (code "40") (name "Net-(P14-Pad3)") (class "Default")
      (node (ref "P14") (pin "3") (pinfunction "3_3") (pintype "passive"))
      (node (ref "U7") (pin "2") (pinfunction "C_2") (pintype "passive"))
    )
    (net (code "41") (name "Net-(P14-Pad4)") (class "Default")
      (node (ref "P14") (pin "4") (pinfunction "4_4") (pintype "passive"))
      (node (ref "R13") (pin "1") (pinfunction "1_1") (pintype "passive"))
    )
    (net (code "42") (name "Net-(P15-Pad1)") (class "Default")
      (node (ref "P15") (pin "1") (pinfunction "1_1") (pintype "passive"))
      (node (ref "U10") (pin "2") (pinfunction "C_2") (pintype "passive"))
    )
    (net (code "43") (name "Net-(P15-Pad2)") (class "Default")
      (node (ref "P15") (pin "2") (pinfunction "2_2") (pintype "passive"))
      (node (ref "R16") (pin "1") (pinfunction "1_1") (pintype "passive"))
    )
    (net (code "44") (name "Net-(P15-Pad3)") (class "Default")
      (node (ref "P15") (pin "3") (pinfunction "3_3") (pintype "passive"))
      (node (ref "U9") (pin "2") (pinfunction "C_2") (pintype "passive"))
    )
    (net (code "45") (name "Net-(P15-Pad4)") (class "Default")
      (node (ref "P15") (pin "4") (pinfunction "4_4") (pintype "passive"))
      (node (ref "R15") (pin "1") (pinfunction "1_1") (pintype "passive"))
    )
    (net (code "46") (name "Net-(P16-Pad1)") (class "Default")
      (node (ref "P16") (pin "1") (pinfunction "1_1") (pintype "passive"))
      (node (ref "U12") (pin "2") (pinfunction "C_2") (pintype "passive"))
    )
    (net (code "47") (name "Net-(P16-Pad2)") (class "Default")
      (node (ref "P16") (pin "2") (pinfunction "2_2") (pintype "passive"))
      (node (ref "R18") (pin "1") (pinfunction "1_1") (pintype "passive"))
    )
    (net (code "48") (name "Net-(P16-Pad3)") (class "Default")
      (node (ref "P16") (pin "3") (pinfunction "3_3") (pintype "passive"))
      (node (ref "U11") (pin "2") (pinfunction "C_2") (pintype "passive"))
    )
    (net (code "49") (name "Net-(P16-Pad4)") (class "Default")
      (node (ref "P16") (pin "4") (pinfunction "4_4") (pintype "passive"))
      (node (ref "R17") (pin "1") (pinfunction "1_1") (pintype "passive"))
    )
    (net (code "50") (name "Net-(P17-Pad1)") (class "Default")
      (node (ref "P17") (pin "1") (pinfunction "1_1") (pintype "passive"))
      (node (ref "RELAY7") (pin "4") (pinfunction "4_4") (pintype "passive"))
    )
    (net (code "51") (name "Net-(P17-Pad2)") (class "Default")
      (node (ref "P17") (pin "2") (pinfunction "2_2") (pintype "passive"))
      (node (ref "P18") (pin "1") (pinfunction "1_1") (pintype "passive"))
    )
    (net (code "52") (name "Net-(P17-Pad3)") (class "Default")
      (node (ref "P17") (pin "3") (pinfunction "3_3") (pintype "passive"))
      (node (ref "RELAY7") (pin "3") (pinfunction "3_3") (pintype "passive"))
    )
    (net (code "53") (name "Net-(P18-Pad2)") (class "Default")
      (node (ref "P18") (pin "2") (pinfunction "2_2") (pintype "passive"))
      (node (ref "RELAY7") (pin "2") (pinfunction "2_2") (pintype "passive"))
    )
    (net (code "54") (name "Net-(P18-Pad3)") (class "Default")
      (node (ref "P18") (pin "3") (pinfunction "3_3") (pintype "passive"))
      (node (ref "RELAY8") (pin "2") (pinfunction "2_2") (pintype "passive"))
    )
    (net (code "55") (name "Net-(P18-Pad4)") (class "Default")
      (node (ref "P18") (pin "4") (pinfunction "4_4") (pintype "passive"))
      (node (ref "P19") (pin "2") (pinfunction "2_2") (pintype "passive"))
    )
    (net (code "56") (name "Net-(P19-Pad1)") (class "Default")
      (node (ref "P19") (pin "1") (pinfunction "1_1") (pintype "passive"))
      (node (ref "RELAY8") (pin "4") (pinfunction "4_4") (pintype "passive"))
    )
    (net (code "57") (name "Net-(P19-Pad3)") (class "Default")
      (node (ref "P19") (pin "3") (pinfunction "3_3") (pintype "passive"))
      (node (ref "RELAY8") (pin "3") (pinfunction "3_3") (pintype "passive"))
    )
    (net (code "58") (name "Net-(P20-Pad1)") (class "Default")
      (node (ref "P20") (pin "1") (pinfunction "1_1") (pintype "passive"))
      (node (ref "RELAY9") (pin "4") (pinfunction "4_4") (pintype "passive"))
    )
    (net (code "59") (name "Net-(P20-Pad2)") (class "Default")
      (node (ref "P20") (pin "2") (pinfunction "2_2") (pintype "passive"))
      (node (ref "P21") (pin "1") (pinfunction "1_1") (pintype "passive"))
    )
    (net (code "60") (name "Net-(P20-Pad3)") (class "Default")
      (node (ref "P20") (pin "3") (pinfunction "3_3") (pintype "passive"))
      (node (ref "RELAY9") (pin "3") (pinfunction "3_3") (pintype "passive"))
    )
    (net (code "61") (name "Net-(P21-Pad2)") (class "Default")
      (node (ref "P21") (pin "2") (pinfunction "2_2") (pintype "passive"))
      (node (ref "RELAY9") (pin "2") (pinfunction "2_2") (pintype "passive"))
    )
    (net (code "62") (name "Net-(P21-Pad3)") (class "Default")
      (node (ref "P21") (pin "3") (pinfunction "3_3") (pintype "passive"))
      (node (ref "RELAY10") (pin "2") (pinfunction "2_2") (pintype "passive"))
    )
    (net (code "63") (name "Net-(P21-Pad4)") (class "Default")
      (node (ref "P21") (pin "4") (pinfunction "4_4") (pintype "passive"))
      (node (ref "P22") (pin "2") (pinfunction "2_2") (pintype "passive"))
    )
    (net (code "64") (name "Net-(P22-Pad1)") (class "Default")
      (node (ref "P22") (pin "1") (pinfunction "1_1") (pintype "passive"))
      (node (ref "RELAY10") (pin "4") (pinfunction "4_4") (pintype "passive"))
    )
    (net (code "65") (name "Net-(P22-Pad3)") (class "Default")
      (node (ref "P22") (pin "3") (pinfunction "3_3") (pintype "passive"))
      (node (ref "RELAY10") (pin "3") (pinfunction "3_3") (pintype "passive"))
    )
    (net (code "66") (name "Net-(P23-Pad1)") (class "Default")
      (node (ref "P23") (pin "1") (pinfunction "1_1") (pintype "passive"))
      (node (ref "RELAY11") (pin "4") (pinfunction "4_4") (pintype "passive"))
    )
    (net (code "67") (name "Net-(P23-Pad2)") (class "Default")
      (node (ref "P23") (pin "2") (pinfunction "2_2") (pintype "passive"))
      (node (ref "P24") (pin "1") (pinfunction "1_1") (pintype "passive"))
    )
    (net (code "68") (name "Net-(P23-Pad3)") (class "Default")
      (node (ref "P23") (pin "3") (pinfunction "3_3") (pintype "passive"))
      (node (ref "RELAY11") (pin "3") (pinfunction "3_3") (pintype "passive"))
    )
    (net (code "69") (name "Net-(P24-Pad2)") (class "Default")
      (node (ref "P24") (pin "2") (pinfunction "2_2") (pintype "passive"))
      (node (ref "RELAY11") (pin "2") (pinfunction "2_2") (pintype "passive"))
    )
    (net (code "70") (name "Net-(P24-Pad3)") (class "Default")
      (node (ref "P24") (pin "3") (pinfunction "3_3") (pintype "passive"))
      (node (ref "RELAY12") (pin "2") (pinfunction "2_2") (pintype "passive"))
    )
    (net (code "71") (name "Net-(P24-Pad4)") (class "Default")
      (node (ref "P24") (pin "4") (pinfunction "4_4") (pintype "passive"))
      (node (ref "P25") (pin "2") (pinfunction "2_2") (pintype "passive"))
    )
    (net (code "72") (name "Net-(P25-Pad1)") (class "Default")
      (node (ref "P25") (pin "1") (pinfunction "1_1") (pintype "passive"))
      (node (ref "RELAY12") (pin "4") (pinfunction "4_4") (pintype "passive"))
    )
    (net (code "73") (name "Net-(P25-Pad3)") (class "Default")
      (node (ref "P25") (pin "3") (pinfunction "3_3") (pintype "passive"))
      (node (ref "RELAY12") (pin "3") (pinfunction "3_3") (pintype "passive"))
    )
    (net (code "74") (name "Net-(P26-Pad1)") (class "Default")
      (node (ref "P26") (pin "1") (pinfunction "1_1") (pintype "passive"))
      (node (ref "U14") (pin "2") (pinfunction "C_2") (pintype "passive"))
    )
    (net (code "75") (name "Net-(P26-Pad2)") (class "Default")
      (node (ref "P26") (pin "2") (pinfunction "2_2") (pintype "passive"))
      (node (ref "R26") (pin "1") (pinfunction "1_1") (pintype "passive"))
    )
    (net (code "76") (name "Net-(P26-Pad3)") (class "Default")
      (node (ref "P26") (pin "3") (pinfunction "3_3") (pintype "passive"))
      (node (ref "U13") (pin "2") (pinfunction "C_2") (pintype "passive"))
    )
    (net (code "77") (name "Net-(P26-Pad4)") (class "Default")
      (node (ref "P26") (pin "4") (pinfunction "4_4") (pintype "passive"))
      (node (ref "R25") (pin "1") (pinfunction "1_1") (pintype "passive"))
    )
    (net (code "78") (name "Net-(P27-Pad1)") (class "Default")
      (node (ref "P27") (pin "1") (pinfunction "1_1") (pintype "passive"))
      (node (ref "U16") (pin "2") (pinfunction "C_2") (pintype "passive"))
    )
    (net (code "79") (name "Net-(P27-Pad2)") (class "Default")
      (node (ref "P27") (pin "2") (pinfunction "2_2") (pintype "passive"))
      (node (ref "R28") (pin "1") (pinfunction "1_1") (pintype "passive"))
    )
    (net (code "80") (name "Net-(P27-Pad3)") (class "Default")
      (node (ref "P27") (pin "3") (pinfunction "3_3") (pintype "passive"))
      (node (ref "U15") (pin "2") (pinfunction "C_2") (pintype "passive"))
    )
    (net (code "81") (name "Net-(P27-Pad4)") (class "Default")
      (node (ref "P27") (pin "4") (pinfunction "4_4") (pintype "passive"))
      (node (ref "R27") (pin "1") (pinfunction "1_1") (pintype "passive"))
    )
    (net (code "82") (name "Net-(P28-Pad1)") (class "Default")
      (node (ref "P28") (pin "1") (pinfunction "1_1") (pintype "passive"))
      (node (ref "RELAY13") (pin "4") (pinfunction "4_4") (pintype "passive"))
    )
    (net (code "83") (name "Net-(P28-Pad2)") (class "Default")
      (node (ref "P28") (pin "2") (pinfunction "2_2") (pintype "passive"))
      (node (ref "P29") (pin "1") (pinfunction "1_1") (pintype "passive"))
    )
    (net (code "84") (name "Net-(P28-Pad3)") (class "Default")
      (node (ref "P28") (pin "3") (pinfunction "3_3") (pintype "passive"))
      (node (ref "RELAY13") (pin "3") (pinfunction "3_3") (pintype "passive"))
    )
    (net (code "85") (name "Net-(P29-Pad2)") (class "Default")
      (node (ref "P29") (pin "2") (pinfunction "2_2") (pintype "passive"))
      (node (ref "RELAY13") (pin "2") (pinfunction "2_2") (pintype "passive"))
    )
    (net (code "86") (name "Net-(P29-Pad3)") (class "Default")
      (node (ref "P29") (pin "3") (pinfunction "3_3") (pintype "passive"))
      (node (ref "RELAY14") (pin "2") (pinfunction "2_2") (pintype "passive"))
    )
    (net (code "87") (name "Net-(P29-Pad4)") (class "Default")
      (node (ref "P29") (pin "4") (pinfunction "4_4") (pintype "passive"))
      (node (ref "P30") (pin "2") (pinfunction "2_2") (pintype "passive"))
    )
    (net (code "88") (name "Net-(P30-Pad1)") (class "Default")
      (node (ref "P30") (pin "1") (pinfunction "1_1") (pintype "passive"))
      (node (ref "RELAY14") (pin "4") (pinfunction "4_4") (pintype "passive"))
    )
    (net (code "89") (name "Net-(P30-Pad3)") (class "Default")
      (node (ref "P30") (pin "3") (pinfunction "3_3") (pintype "passive"))
      (node (ref "RELAY14") (pin "3") (pinfunction "3_3") (pintype "passive"))
    )
    (net (code "90") (name "Net-(P31-Pad1)") (class "Default")
      (node (ref "P31") (pin "1") (pinfunction "1_1") (pintype "passive"))
      (node (ref "RELAY15") (pin "4") (pinfunction "4_4") (pintype "passive"))
    )
    (net (code "91") (name "Net-(P31-Pad2)") (class "Default")
      (node (ref "P31") (pin "2") (pinfunction "2_2") (pintype "passive"))
      (node (ref "P32") (pin "1") (pinfunction "1_1") (pintype "passive"))
    )
    (net (code "92") (name "Net-(P31-Pad3)") (class "Default")
      (node (ref "P31") (pin "3") (pinfunction "3_3") (pintype "passive"))
      (node (ref "RELAY15") (pin "3") (pinfunction "3_3") (pintype "passive"))
    )
    (net (code "93") (name "Net-(P32-Pad2)") (class "Default")
      (node (ref "P32") (pin "2") (pinfunction "2_2") (pintype "passive"))
      (node (ref "RELAY15") (pin "2") (pinfunction "2_2") (pintype "passive"))
    )
    (net (code "94") (name "Net-(P32-Pad3)") (class "Default")
      (node (ref "P32") (pin "3") (pinfunction "3_3") (pintype "passive"))
      (node (ref "RELAY16") (pin "2") (pinfunction "2_2") (pintype "passive"))
    )
    (net (code "95") (name "Net-(P32-Pad4)") (class "Default")
      (node (ref "P32") (pin "4") (pinfunction "4_4") (pintype "passive"))
      (node (ref "P33") (pin "2") (pinfunction "2_2") (pintype "passive"))
    )
    (net (code "96") (name "Net-(P33-Pad1)") (class "Default")
      (node (ref "P33") (pin "1") (pinfunction "1_1") (pintype "passive"))
      (node (ref "RELAY16") (pin "4") (pinfunction "4_4") (pintype "passive"))
    )
    (net (code "97") (name "Net-(P33-Pad3)") (class "Default")
      (node (ref "P33") (pin "3") (pinfunction "3_3") (pintype "passive"))
      (node (ref "RELAY16") (pin "3") (pinfunction "3_3") (pintype "passive"))
    )
    (net (code "98") (name "Net-(Q1-B)") (class "Default")
      (node (ref "Q1") (pin "3") (pinfunction "B_3") (pintype "passive"))
      (node (ref "R33") (pin "2") (pinfunction "2_2") (pintype "passive"))
      (node (ref "R7") (pin "2") (pinfunction "2_2") (pintype "passive"))
    )
    (net (code "99") (name "Net-(Q1-C)") (class "Default")
      (node (ref "Q1") (pin "2") (pinfunction "C_2") (pintype "passive"))
      (node (ref "RELAY1") (pin "1") (pinfunction "1_1") (pintype "passive"))
    )
    (net (code "100") (name "Net-(Q2-B)") (class "Default")
      (node (ref "Q2") (pin "3") (pinfunction "B_3") (pintype "passive"))
      (node (ref "R34") (pin "2") (pinfunction "2_2") (pintype "passive"))
      (node (ref "R8") (pin "2") (pinfunction "2_2") (pintype "passive"))
    )
    (net (code "101") (name "Net-(Q2-C)") (class "Default")
      (node (ref "Q2") (pin "2") (pinfunction "C_2") (pintype "passive"))
      (node (ref "RELAY2") (pin "1") (pinfunction "1_1") (pintype "passive"))
    )
    (net (code "102") (name "Net-(Q3-B)") (class "Default")
      (node (ref "Q3") (pin "3") (pinfunction "B_3") (pintype "passive"))
      (node (ref "R35") (pin "2") (pinfunction "2_2") (pintype "passive"))
      (node (ref "R9") (pin "2") (pinfunction "2_2") (pintype "passive"))
    )
    (net (code "103") (name "Net-(Q3-C)") (class "Default")
      (node (ref "Q3") (pin "2") (pinfunction "C_2") (pintype "passive"))
      (node (ref "RELAY3") (pin "1") (pinfunction "1_1") (pintype "passive"))
    )
    (net (code "104") (name "Net-(Q4-B)") (class "Default")
      (node (ref "Q4") (pin "3") (pinfunction "B_3") (pintype "passive"))
      (node (ref "R10") (pin "2") (pinfunction "2_2") (pintype "passive"))
      (node (ref "R36") (pin "2") (pinfunction "2_2") (pintype "passive"))
    )
    (net (code "105") (name "Net-(Q4-C)") (class "Default")
      (node (ref "Q4") (pin "2") (pinfunction "C_2") (pintype "passive"))
      (node (ref "RELAY4") (pin "1") (pinfunction "1_1") (pintype "passive"))
    )
    (net (code "106") (name "Net-(Q5-B)") (class "Default")
      (node (ref "Q5") (pin "3") (pinfunction "B_3") (pintype "passive"))
      (node (ref "R11") (pin "2") (pinfunction "2_2") (pintype "passive"))
      (node (ref "R37") (pin "2") (pinfunction "2_2") (pintype "passive"))
    )
    (net (code "107") (name "Net-(Q5-C)") (class "Default")
      (node (ref "Q5") (pin "2") (pinfunction "C_2") (pintype "passive"))
      (node (ref "RELAY5") (pin "1") (pinfunction "1_1") (pintype "passive"))
    )
    (net (code "108") (name "Net-(Q6-B)") (class "Default")
      (node (ref "Q6") (pin "3") (pinfunction "B_3") (pintype "passive"))
      (node (ref "R12") (pin "2") (pinfunction "2_2") (pintype "passive"))
      (node (ref "R38") (pin "2") (pinfunction "2_2") (pintype "passive"))
    )
    (net (code "109") (name "Net-(Q6-C)") (class "Default")
      (node (ref "Q6") (pin "2") (pinfunction "C_2") (pintype "passive"))
      (node (ref "RELAY6") (pin "1") (pinfunction "1_1") (pintype "passive"))
    )
    (net (code "110") (name "Net-(Q7-B)") (class "Default")
      (node (ref "Q7") (pin "3") (pinfunction "B_3") (pintype "passive"))
      (node (ref "R19") (pin "2") (pinfunction "2_2") (pintype "passive"))
      (node (ref "R39") (pin "2") (pinfunction "2_2") (pintype "passive"))
    )
    (net (code "111") (name "Net-(Q7-C)") (class "Default")
      (node (ref "Q7") (pin "2") (pinfunction "C_2") (pintype "passive"))
      (node (ref "RELAY7") (pin "1") (pinfunction "1_1") (pintype "passive"))
    )
    (net (code "112") (name "Net-(Q8-B)") (class "Default")
      (node (ref "Q8") (pin "3") (pinfunction "B_3") (pintype "passive"))
      (node (ref "R20") (pin "2") (pinfunction "2_2") (pintype "passive"))
      (node (ref "R40") (pin "2") (pinfunction "2_2") (pintype "passive"))
    )
    (net (code "113") (name "Net-(Q8-C)") (class "Default")
      (node (ref "Q8") (pin "2") (pinfunction "C_2") (pintype "passive"))
      (node (ref "RELAY8") (pin "1") (pinfunction "1_1") (pintype "passive"))
    )
    (net (code "114") (name "Net-(Q9-B)") (class "Default")
      (node (ref "Q9") (pin "3") (pinfunction "B_3") (pintype "passive"))
      (node (ref "R21") (pin "2") (pinfunction "2_2") (pintype "passive"))
      (node (ref "R41") (pin "2") (pinfunction "2_2") (pintype "passive"))
    )
    (net (code "115") (name "Net-(Q9-C)") (class "Default")
      (node (ref "Q9") (pin "2") (pinfunction "C_2") (pintype "passive"))
      (node (ref "RELAY9") (pin "1") (pinfunction "1_1") (pintype "passive"))
    )
    (net (code "116") (name "Net-(Q10-B)") (class "Default")
      (node (ref "Q10") (pin "3") (pinfunction "B_3") (pintype "passive"))
      (node (ref "R22") (pin "2") (pinfunction "2_2") (pintype "passive"))
      (node (ref "R42") (pin "2") (pinfunction "2_2") (pintype "passive"))
    )
    (net (code "117") (name "Net-(Q10-C)") (class "Default")
      (node (ref "Q10") (pin "2") (pinfunction "C_2") (pintype "passive"))
      (node (ref "RELAY10") (pin "1") (pinfunction "1_1") (pintype "passive"))
    )
    (net (code "118") (name "Net-(Q11-B)") (class "Default")
      (node (ref "Q11") (pin "3") (pinfunction "B_3") (pintype "passive"))
      (node (ref "R23") (pin "2") (pinfunction "2_2") (pintype "passive"))
      (node (ref "R43") (pin "2") (pinfunction "2_2") (pintype "passive"))
    )
    (net (code "119") (name "Net-(Q11-C)") (class "Default")
      (node (ref "Q11") (pin "2") (pinfunction "C_2") (pintype "passive"))
      (node (ref "RELAY11") (pin "1") (pinfunction "1_1") (pintype "passive"))
    )
    (net (code "120") (name "Net-(Q12-B)") (class "Default")
      (node (ref "Q12") (pin "3") (pinfunction "B_3") (pintype "passive"))
      (node (ref "R24") (pin "2") (pinfunction "2_2") (pintype "passive"))
      (node (ref "R44") (pin "2") (pinfunction "2_2") (pintype "passive"))
    )
    (net (code "121") (name "Net-(Q12-C)") (class "Default")
      (node (ref "Q12") (pin "2") (pinfunction "C_2") (pintype "passive"))
      (node (ref "RELAY12") (pin "1") (pinfunction "1_1") (pintype "passive"))
    )
    (net (code "122") (name "Net-(Q13-B)") (class "Default")
      (node (ref "Q13") (pin "3") (pinfunction "B_3") (pintype "passive"))
      (node (ref "R29") (pin "2") (pinfunction "2_2") (pintype "passive"))
      (node (ref "R45") (pin "2") (pinfunction "2_2") (pintype "passive"))
    )
    (net (code "123") (name "Net-(Q13-C)") (class "Default")
      (node (ref "Q13") (pin "2") (pinfunction "C_2") (pintype "passive"))
      (node (ref "RELAY13") (pin "1") (pinfunction "1_1") (pintype "passive"))
    )
    (net (code "124") (name "Net-(Q14-B)") (class "Default")
      (node (ref "Q14") (pin "3") (pinfunction "B_3") (pintype "passive"))
      (node (ref "R30") (pin "2") (pinfunction "2_2") (pintype "passive"))
      (node (ref "R46") (pin "2") (pinfunction "2_2") (pintype "passive"))
    )
    (net (code "125") (name "Net-(Q14-C)") (class "Default")
      (node (ref "Q14") (pin "2") (pinfunction "C_2") (pintype "passive"))
      (node (ref "RELAY14") (pin "1") (pinfunction "1_1") (pintype "passive"))
    )
    (net (code "126") (name "Net-(Q15-B)") (class "Default")
      (node (ref "Q15") (pin "3") (pinfunction "B_3") (pintype "passive"))
      (node (ref "R31") (pin "2") (pinfunction "2_2") (pintype "passive"))
      (node (ref "R47") (pin "2") (pinfunction "2_2") (pintype "passive"))
    )
    (net (code "127") (name "Net-(Q15-C)") (class "Default")
      (node (ref "Q15") (pin "2") (pinfunction "C_2") (pintype "passive"))
      (node (ref "RELAY15") (pin "1") (pinfunction "1_1") (pintype "passive"))
    )
    (net (code "128") (name "Net-(Q16-B)") (class "Default")
      (node (ref "Q16") (pin "3") (pinfunction "B_3") (pintype "passive"))
      (node (ref "R32") (pin "2") (pinfunction "2_2") (pintype "passive"))
      (node (ref "R48") (pin "2") (pinfunction "2_2") (pintype "passive"))
    )
    (net (code "129") (name "Net-(Q16-C)") (class "Default")
      (node (ref "Q16") (pin "2") (pinfunction "C_2") (pintype "passive"))
      (node (ref "RELAY16") (pin "1") (pinfunction "1_1") (pintype "passive"))
    )
    (net (code "130") (name "Net-(U1-A)") (class "Default")
      (node (ref "R1") (pin "2") (pinfunction "2_2") (pintype "passive"))
      (node (ref "U1") (pin "1") (pinfunction "A_1") (pintype "passive"))
    )
    (net (code "131") (name "Net-(U1-E)") (class "Default")
      (node (ref "R7") (pin "1") (pinfunction "1_1") (pintype "passive"))
      (node (ref "U1") (pin "3") (pinfunction "E_3") (pintype "passive"))
    )
    (net (code "132") (name "Net-(U2-A)") (class "Default")
      (node (ref "R2") (pin "2") (pinfunction "2_2") (pintype "passive"))
      (node (ref "U2") (pin "1") (pinfunction "A_1") (pintype "passive"))
    )
    (net (code "133") (name "Net-(U2-E)") (class "Default")
      (node (ref "R8") (pin "1") (pinfunction "1_1") (pintype "passive"))
      (node (ref "U2") (pin "3") (pinfunction "E_3") (pintype "passive"))
    )
    (net (code "134") (name "Net-(U3-A)") (class "Default")
      (node (ref "R3") (pin "2") (pinfunction "2_2") (pintype "passive"))
      (node (ref "U3") (pin "1") (pinfunction "A_1") (pintype "passive"))
    )
    (net (code "135") (name "Net-(U3-E)") (class "Default")
      (node (ref "R9") (pin "1") (pinfunction "1_1") (pintype "passive"))
      (node (ref "U3") (pin "3") (pinfunction "E_3") (pintype "passive"))
    )
    (net (code "136") (name "Net-(U4-A)") (class "Default")
      (node (ref "R4") (pin "2") (pinfunction "2_2") (pintype "passive"))
      (node (ref "U4") (pin "1") (pinfunction "A_1") (pintype "passive"))
    )
    (net (code "137") (name "Net-(U4-E)") (class "Default")
      (node (ref "R10") (pin "1") (pinfunction "1_1") (pintype "passive"))
      (node (ref "U4") (pin "3") (pinfunction "E_3") (pintype "passive"))
    )
    (net (code "138") (name "Net-(U5-A)") (class "Default")
      (node (ref "R5") (pin "2") (pinfunction "2_2") (pintype "passive"))
      (node (ref "U5") (pin "1") (pinfunction "A_1") (pintype "passive"))
    )
    (net (code "139") (name "Net-(U5-E)") (class "Default")
      (node (ref "R11") (pin "1") (pinfunction "1_1") (pintype "passive"))
      (node (ref "U5") (pin "3") (pinfunction "E_3") (pintype "passive"))
    )
    (net (code "140") (name "Net-(U6-A)") (class "Default")
      (node (ref "R6") (pin "2") (pinfunction "2_2") (pintype "passive"))
      (node (ref "U6") (pin "1") (pinfunction "A_1") (pintype "passive"))
    )
    (net (code "141") (name "Net-(U6-E)") (class "Default")
      (node (ref "R12") (pin "1") (pinfunction "1_1") (pintype "passive"))
      (node (ref "U6") (pin "3") (pinfunction "E_3") (pintype "passive"))
    )
    (net (code "142") (name "Net-(U7-A)") (class "Default")
      (node (ref "R13") (pin "2") (pinfunction "2_2") (pintype "passive"))
      (node (ref "U7") (pin "1") (pinfunction "A_1") (pintype "passive"))
    )
    (net (code "143") (name "Net-(U7-E)") (class "Default")
      (node (ref "R19") (pin "1") (pinfunction "1_1") (pintype "passive"))
      (node (ref "U7") (pin "3") (pinfunction "E_3") (pintype "passive"))
    )
    (net (code "144") (name "Net-(U8-A)") (class "Default")
      (node (ref "R14") (pin "2") (pinfunction "2_2") (pintype "passive"))
      (node (ref "U8") (pin "1") (pinfunction "A_1") (pintype "passive"))
    )
    (net (code "145") (name "Net-(U8-E)") (class "Default")
      (node (ref "R20") (pin "1") (pinfunction "1_1") (pintype "passive"))
      (node (ref "U8") (pin "3") (pinfunction "E_3") (pintype "passive"))
    )
    (net (code "146") (name "Net-(U9-A)") (class "Default")
      (node (ref "R15") (pin "2") (pinfunction "2_2") (pintype "passive"))
      (node (ref "U9") (pin "1") (pinfunction "A_1") (pintype "passive"))
    )
    (net (code "147") (name "Net-(U9-E)") (class "Default")
      (node (ref "R21") (pin "1") (pinfunction "1_1") (pintype "passive"))
      (node (ref "U9") (pin "3") (pinfunction "E_3") (pintype "passive"))
    )
    (net (code "148") (name "Net-(U10-A)") (class "Default")
      (node (ref "R16") (pin "2") (pinfunction "2_2") (pintype "passive"))
      (node (ref "U10") (pin "1") (pinfunction "A_1") (pintype "passive"))
    )
    (net (code "149") (name "Net-(U10-E)") (class "Default")
      (node (ref "R22") (pin "1") (pinfunction "1_1") (pintype "passive"))
      (node (ref "U10") (pin "3") (pinfunction "E_3") (pintype "passive"))
    )
    (net (code "150") (name "Net-(U11-A)") (class "Default")
      (node (ref "R17") (pin "2") (pinfunction "2_2") (pintype "passive"))
      (node (ref "U11") (pin "1") (pinfunction "A_1") (pintype "passive"))
    )
    (net (code "151") (name "Net-(U11-E)") (class "Default")
      (node (ref "R23") (pin "1") (pinfunction "1_1") (pintype "passive"))
      (node (ref "U11") (pin "3") (pinfunction "E_3") (pintype "passive"))
    )
    (net (code "152") (name "Net-(U12-A)") (class "Default")
      (node (ref "R18") (pin "2") (pinfunction "2_2") (pintype "passive"))
      (node (ref "U12") (pin "1") (pinfunction "A_1") (pintype "passive"))
    )
    (net (code "153") (name "Net-(U12-E)") (class "Default")
      (node (ref "R24") (pin "1") (pinfunction "1_1") (pintype "passive"))
      (node (ref "U12") (pin "3") (pinfunction "E_3") (pintype "passive"))
    )
    (net (code "154") (name "Net-(U13-A)") (class "Default")
      (node (ref "R25") (pin "2") (pinfunction "2_2") (pintype "passive"))
      (node (ref "U13") (pin "1") (pinfunction "A_1") (pintype "passive"))
    )
    (net (code "155") (name "Net-(U13-E)") (class "Default")
      (node (ref "R29") (pin "1") (pinfunction "1_1") (pintype "passive"))
      (node (ref "U13") (pin "3") (pinfunction "E_3") (pintype "passive"))
    )
    (net (code "156") (name "Net-(U14-A)") (class "Default")
      (node (ref "R26") (pin "2") (pinfunction "2_2") (pintype "passive"))
      (node (ref "U14") (pin "1") (pinfunction "A_1") (pintype "passive"))
    )
    (net (code "157") (name "Net-(U14-E)") (class "Default")
      (node (ref "R30") (pin "1") (pinfunction "1_1") (pintype "passive"))
      (node (ref "U14") (pin "3") (pinfunction "E_3") (pintype "passive"))
    )
    (net (code "158") (name "Net-(U15-A)") (class "Default")
      (node (ref "R27") (pin "2") (pinfunction "2_2") (pintype "passive"))
      (node (ref "U15") (pin "1") (pinfunction "A_1") (pintype "passive"))
    )
    (net (code "159") (name "Net-(U15-E)") (class "Default")
      (node (ref "R31") (pin "1") (pinfunction "1_1") (pintype "passive"))
      (node (ref "U15") (pin "3") (pinfunction "E_3") (pintype "passive"))
    )
    (net (code "160") (name "Net-(U16-A)") (class "Default")
      (node (ref "R28") (pin "2") (pinfunction "2_2") (pintype "passive"))
      (node (ref "U16") (pin "1") (pinfunction "A_1") (pintype "passive"))
    )
    (net (code "161") (name "Net-(U16-E)") (class "Default")
      (node (ref "R32") (pin "1") (pinfunction "1_1") (pintype "passive"))
      (node (ref "U16") (pin "3") (pinfunction "E_3") (pintype "passive"))
    )
    (net (code "162") (name "VCC") (class "Default")
      (node (ref "C1") (pin "2") (pinfunction "2_2") (pintype "passive"))
      (node (ref "D1") (pin "2") (pinfunction "K_2") (pintype "passive"))
      (node (ref "P1") (pin "2") (pinfunction "2_2") (pintype "passive"))
      (node (ref "RELAY1") (pin "8") (pinfunction "8_8") (pintype "passive"))
      (node (ref "RELAY10") (pin "8") (pinfunction "8_8") (pintype "passive"))
      (node (ref "RELAY11") (pin "8") (pinfunction "8_8") (pintype "passive"))
      (node (ref "RELAY12") (pin "8") (pinfunction "8_8") (pintype "passive"))
      (node (ref "RELAY13") (pin "8") (pinfunction "8_8") (pintype "passive"))
      (node (ref "RELAY14") (pin "8") (pinfunction "8_8") (pintype "passive"))
      (node (ref "RELAY15") (pin "8") (pinfunction "8_8") (pintype "passive"))
      (node (ref "RELAY16") (pin "8") (pinfunction "8_8") (pintype "passive"))
      (node (ref "RELAY2") (pin "8") (pinfunction "8_8") (pintype "passive"))
      (node (ref "RELAY3") (pin "8") (pinfunction "8_8") (pintype "passive"))
      (node (ref "RELAY4") (pin "8") (pinfunction "8_8") (pintype "passive"))
      (node (ref "RELAY5") (pin "8") (pinfunction "8_8") (pintype "passive"))
      (node (ref "RELAY6") (pin "8") (pinfunction "8_8") (pintype "passive"))
      (node (ref "RELAY7") (pin "8") (pinfunction "8_8") (pintype "passive"))
      (node (ref "RELAY8") (pin "8") (pinfunction "8_8") (pintype "passive"))
      (node (ref "RELAY9") (pin "8") (pinfunction "8_8") (pintype "passive"))
      (node (ref "U1") (pin "4") (pinfunction "C_4") (pintype "passive"))
      (node (ref "U10") (pin "4") (pinfunction "C_4") (pintype "passive"))
      (node (ref "U11") (pin "4") (pinfunction "C_4") (pintype "passive"))
      (node (ref "U12") (pin "4") (pinfunction "C_4") (pintype "passive"))
      (node (ref "U13") (pin "4") (pinfunction "C_4") (pintype "passive"))
      (node (ref "U14") (pin "4") (pinfunction "C_4") (pintype "passive"))
      (node (ref "U15") (pin "4") (pinfunction "C_4") (pintype "passive"))
      (node (ref "U16") (pin "4") (pinfunction "C_4") (pintype "passive"))
      (node (ref "U2") (pin "4") (pinfunction "C_4") (pintype "passive"))
      (node (ref "U3") (pin "4") (pinfunction "C_4") (pintype "passive"))
      (node (ref "U4") (pin "4") (pinfunction "C_4") (pintype "passive"))
      (node (ref "U5") (pin "4") (pinfunction "C_4") (pintype "passive"))
      (node (ref "U6") (pin "4") (pinfunction "C_4") (pintype "passive"))
      (node (ref "U7") (pin "4") (pinfunction "C_4") (pintype "passive"))
      (node (ref "U8") (pin "4") (pinfunction "C_4") (pintype "passive"))
      (node (ref "U9") (pin "4") (pinfunction "C_4") (pintype "passive"))
    )
    (net (code "163") (name "unconnected-(RELAY1-Pad5)") (class "Default")
      (node (ref "RELAY1") (pin "5") (pinfunction "5_5") (pintype "passive"))
    )
    (net (code "164") (name "unconnected-(RELAY1-Pad6)") (class "Default")
      (node (ref "RELAY1") (pin "6") (pinfunction "6_6") (pintype "passive"))
    )
    (net (code "165") (name "unconnected-(RELAY1-Pad7)") (class "Default")
      (node (ref "RELAY1") (pin "7") (pinfunction "7_7") (pintype "passive"))
    )
    (net (code "166") (name "unconnected-(RELAY2-Pad5)") (class "Default")
      (node (ref "RELAY2") (pin "5") (pinfunction "5_5") (pintype "passive"))
    )
    (net (code "167") (name "unconnected-(RELAY2-Pad6)") (class "Default")
      (node (ref "RELAY2") (pin "6") (pinfunction "6_6") (pintype "passive"))
    )
    (net (code "168") (name "unconnected-(RELAY2-Pad7)") (class "Default")
      (node (ref "RELAY2") (pin "7") (pinfunction "7_7") (pintype "passive"))
    )
    (net (code "169") (name "unconnected-(RELAY3-Pad5)") (class "Default")
      (node (ref "RELAY3") (pin "5") (pinfunction "5_5") (pintype "passive"))
    )
    (net (code "170") (name "unconnected-(RELAY3-Pad6)") (class "Default")
      (node (ref "RELAY3") (pin "6") (pinfunction "6_6") (pintype "passive"))
    )
    (net (code "171") (name "unconnected-(RELAY3-Pad7)") (class "Default")
      (node (ref "RELAY3") (pin "7") (pinfunction "7_7") (pintype "passive"))
    )
    (net (code "172") (name "unconnected-(RELAY4-Pad5)") (class "Default")
      (node (ref "RELAY4") (pin "5") (pinfunction "5_5") (pintype "passive"))
    )
    (net (code "173") (name "unconnected-(RELAY4-Pad6)") (class "Default")
      (node (ref "RELAY4") (pin "6") (pinfunction "6_6") (pintype "passive"))
    )
    (net (code "174") (name "unconnected-(RELAY4-Pad7)") (class "Default")
      (node (ref "RELAY4") (pin "7") (pinfunction "7_7") (pintype "passive"))
    )
    (net (code "175") (name "unconnected-(RELAY5-Pad5)") (class "Default")
      (node (ref "RELAY5") (pin "5") (pinfunction "5_5") (pintype "passive"))
    )
    (net (code "176") (name "unconnected-(RELAY5-Pad6)") (class "Default")
      (node (ref "RELAY5") (pin "6") (pinfunction "6_6") (pintype "passive"))
    )
    (net (code "177") (name "unconnected-(RELAY5-Pad7)") (class "Default")
      (node (ref "RELAY5") (pin "7") (pinfunction "7_7") (pintype "passive"))
    )
    (net (code "178") (name "unconnected-(RELAY6-Pad5)") (class "Default")
      (node (ref "RELAY6") (pin "5") (pinfunction "5_5") (pintype "passive"))
    )
    (net (code "179") (name "unconnected-(RELAY6-Pad6)") (class "Default")
      (node (ref "RELAY6") (pin "6") (pinfunction "6_6") (pintype "passive"))
    )
    (net (code "180") (name "unconnected-(RELAY6-Pad7)") (class "Default")
      (node (ref "RELAY6") (pin "7") (pinfunction "7_7") (pintype "passive"))
    )
    (net (code "181") (name "unconnected-(RELAY7-Pad5)") (class "Default")
      (node (ref "RELAY7") (pin "5") (pinfunction "5_5") (pintype "passive"))
    )
    (net (code "182") (name "unconnected-(RELAY7-Pad6)") (class "Default")
      (node (ref "RELAY7") (pin "6") (pinfunction "6_6") (pintype "passive"))
    )
    (net (code "183") (name "unconnected-(RELAY7-Pad7)") (class "Default")
      (node (ref "RELAY7") (pin "7") (pinfunction "7_7") (pintype "passive"))
    )
    (net (code "184") (name "unconnected-(RELAY8-Pad5)") (class "Default")
      (node (ref "RELAY8") (pin "5") (pinfunction "5_5") (pintype "passive"))
    )
    (net (code "185") (name "unconnected-(RELAY8-Pad6)") (class "Default")
      (node (ref "RELAY8") (pin "6") (pinfunction "6_6") (pintype "passive"))
    )
    (net (code "186") (name "unconnected-(RELAY8-Pad7)") (class "Default")
      (node (ref "RELAY8") (pin "7") (pinfunction "7_7") (pintype "passive"))
    )
    (net (code "187") (name "unconnected-(RELAY9-Pad5)") (class "Default")
      (node (ref "RELAY9") (pin "5") (pinfunction "5_5") (pintype "passive"))
    )
    (net (code "188") (name "unconnected-(RELAY9-Pad6)") (class "Default")
      (node (ref "RELAY9") (pin "6") (pinfunction "6_6") (pintype "passive"))
    )
    (net (code "189") (name "unconnected-(RELAY9-Pad7)") (class "Default")
      (node (ref "RELAY9") (pin "7") (pinfunction "7_7") (pintype "passive"))
    )
    (net (code "190") (name "unconnected-(RELAY10-Pad5)") (class "Default")
      (node (ref "RELAY10") (pin "5") (pinfunction "5_5") (pintype "passive"))
    )
    (net (code "191") (name "unconnected-(RELAY10-Pad6)") (class "Default")
      (node (ref "RELAY10") (pin "6") (pinfunction "6_6") (pintype "passive"))
    )
    (net (code "192") (name "unconnected-(RELAY10-Pad7)") (class "Default")
      (node (ref "RELAY10") (pin "7") (pinfunction "7_7") (pintype "passive"))
    )
    (net (code "193") (name "unconnected-(RELAY11-Pad5)") (class "Default")
      (node (ref "RELAY11") (pin "5") (pinfunction "5_5") (pintype "passive"))
    )
    (net (code "194") (name "unconnected-(RELAY11-Pad6)") (class "Default")
      (node (ref "RELAY11") (pin "6") (pinfunction "6_6") (pintype "passive"))
    )
    (net (code "195") (name "unconnected-(RELAY11-Pad7)") (class "Default")
      (node (ref "RELAY11") (pin "7") (pinfunction "7_7") (pintype "passive"))
    )
    (net (code "196") (name "unconnected-(RELAY12-Pad5)") (class "Default")
      (node (ref "RELAY12") (pin "5") (pinfunction "5_5") (pintype "passive"))
    )
    (net (code "197") (name "unconnected-(RELAY12-Pad6)") (class "Default")
      (node (ref "RELAY12") (pin "6") (pinfunction "6_6") (pintype "passive"))
    )
    (net (code "198") (name "unconnected-(RELAY12-Pad7)") (class "Default")
      (node (ref "RELAY12") (pin "7") (pinfunction "7_7") (pintype "passive"))
    )
    (net (code "199") (name "unconnected-(RELAY13-Pad5)") (class "Default")
      (node (ref "RELAY13") (pin "5") (pinfunction "5_5") (pintype "passive"))
    )
    (net (code "200") (name "unconnected-(RELAY13-Pad6)") (class "Default")
      (node (ref "RELAY13") (pin "6") (pinfunction "6_6") (pintype "passive"))
    )
    (net (code "201") (name "unconnected-(RELAY13-Pad7)") (class "Default")
      (node (ref "RELAY13") (pin "7") (pinfunction "7_7") (pintype "passive"))
    )
    (net (code "202") (name "unconnected-(RELAY14-Pad5)") (class "Default")
      (node (ref "RELAY14") (pin "5") (pinfunction "5_5") (pintype "passive"))
    )
    (net (code "203") (name "unconnected-(RELAY14-Pad6)") (class "Default")
      (node (ref "RELAY14") (pin "6") (pinfunction "6_6") (pintype "passive"))
    )
    (net (code "204") (name "unconnected-(RELAY14-Pad7)") (class "Default")
      (node (ref "RELAY14") (pin "7") (pinfunction "7_7") (pintype "passive"))
    )
    (net (code "205") (name "unconnected-(RELAY15-Pad5)") (class "Default")
      (node (ref "RELAY15") (pin "5") (pinfunction "5_5") (pintype "passive"))
    )
    (net (code "206") (name "unconnected-(RELAY15-Pad6)") (class "Default")
      (node (ref "RELAY15") (pin "6") (pinfunction "6_6") (pintype "passive"))
    )
    (net (code "207") (name "unconnected-(RELAY15-Pad7)") (class "Default")
      (node (ref "RELAY15") (pin "7") (pinfunction "7_7") (pintype "passive"))
    )
    (net (code "208") (name "unconnected-(RELAY16-Pad5)") (class "Default")
      (node (ref "RELAY16") (pin "5") (pinfunction "5_5") (pintype "passive"))
    )
    (net (code "209") (name "unconnected-(RELAY16-Pad6)") (class "Default")
      (node (ref "RELAY16") (pin "6") (pinfunction "6_6") (pintype "passive"))
    )
    (net (code "210") (name "unconnected-(RELAY16-Pad7)") (class "Default")
      (node (ref "RELAY16") (pin "7") (pinfunction "7_7") (pintype "passive"))
    )
  )
)
